# SoC_pwr_1.net
KiCad netlist of a schematic drawn in Altium Designer
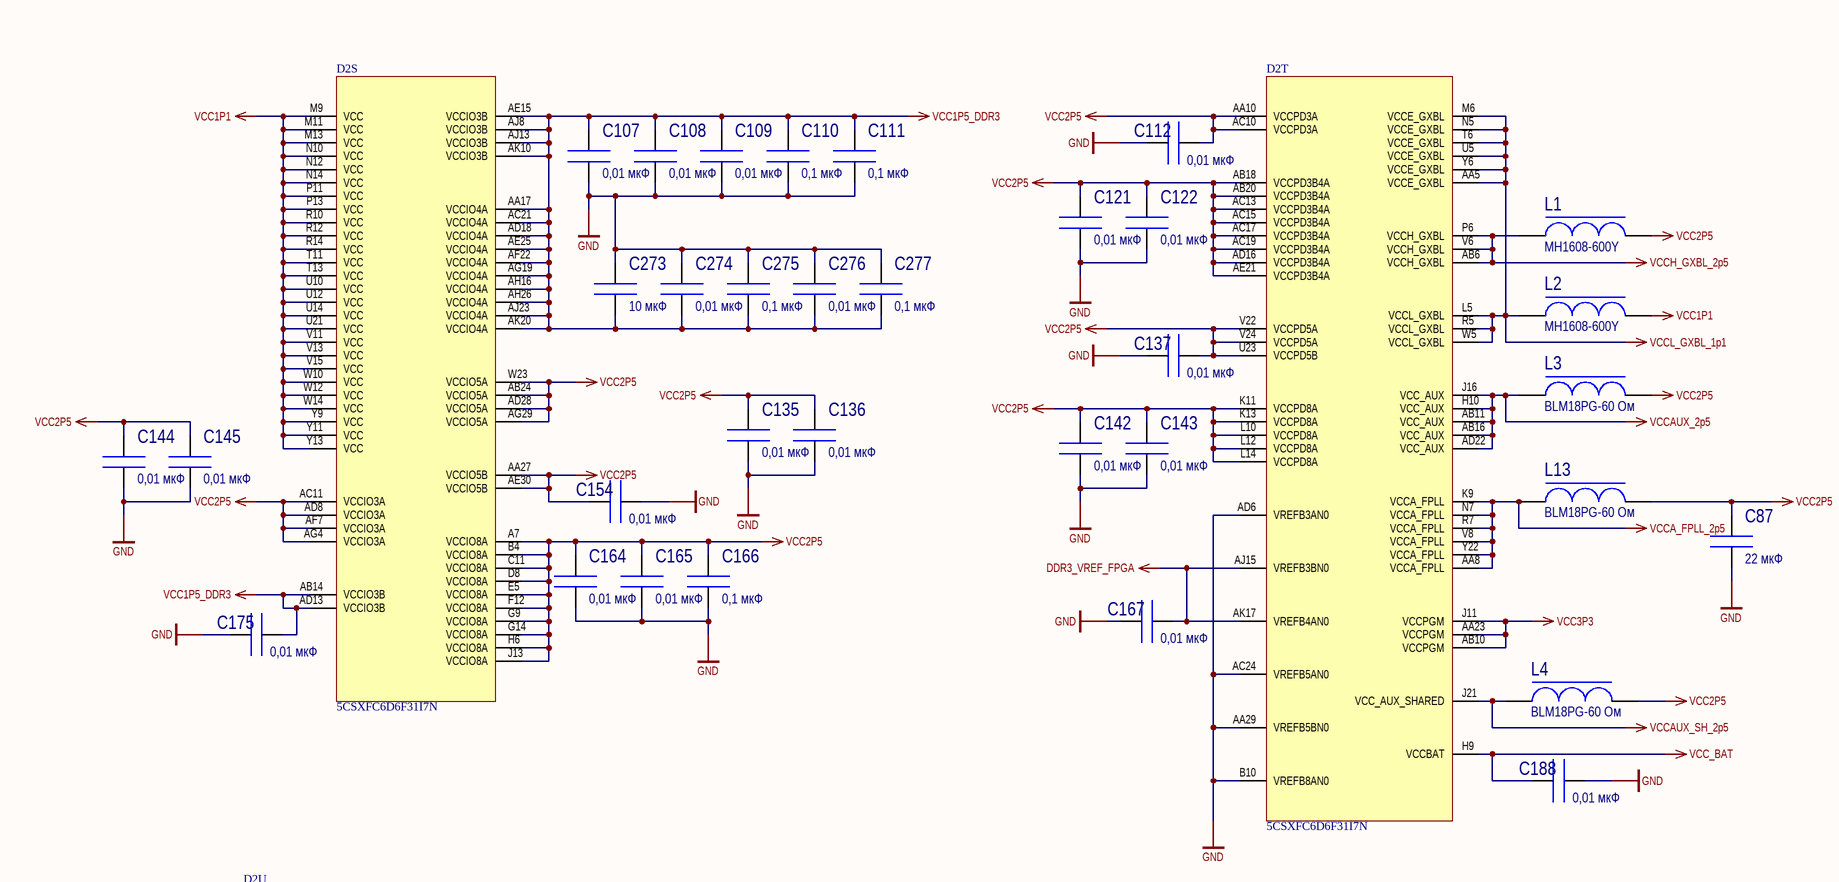
[diagram p0: SoC_pwr_1.SchDoc, top left]
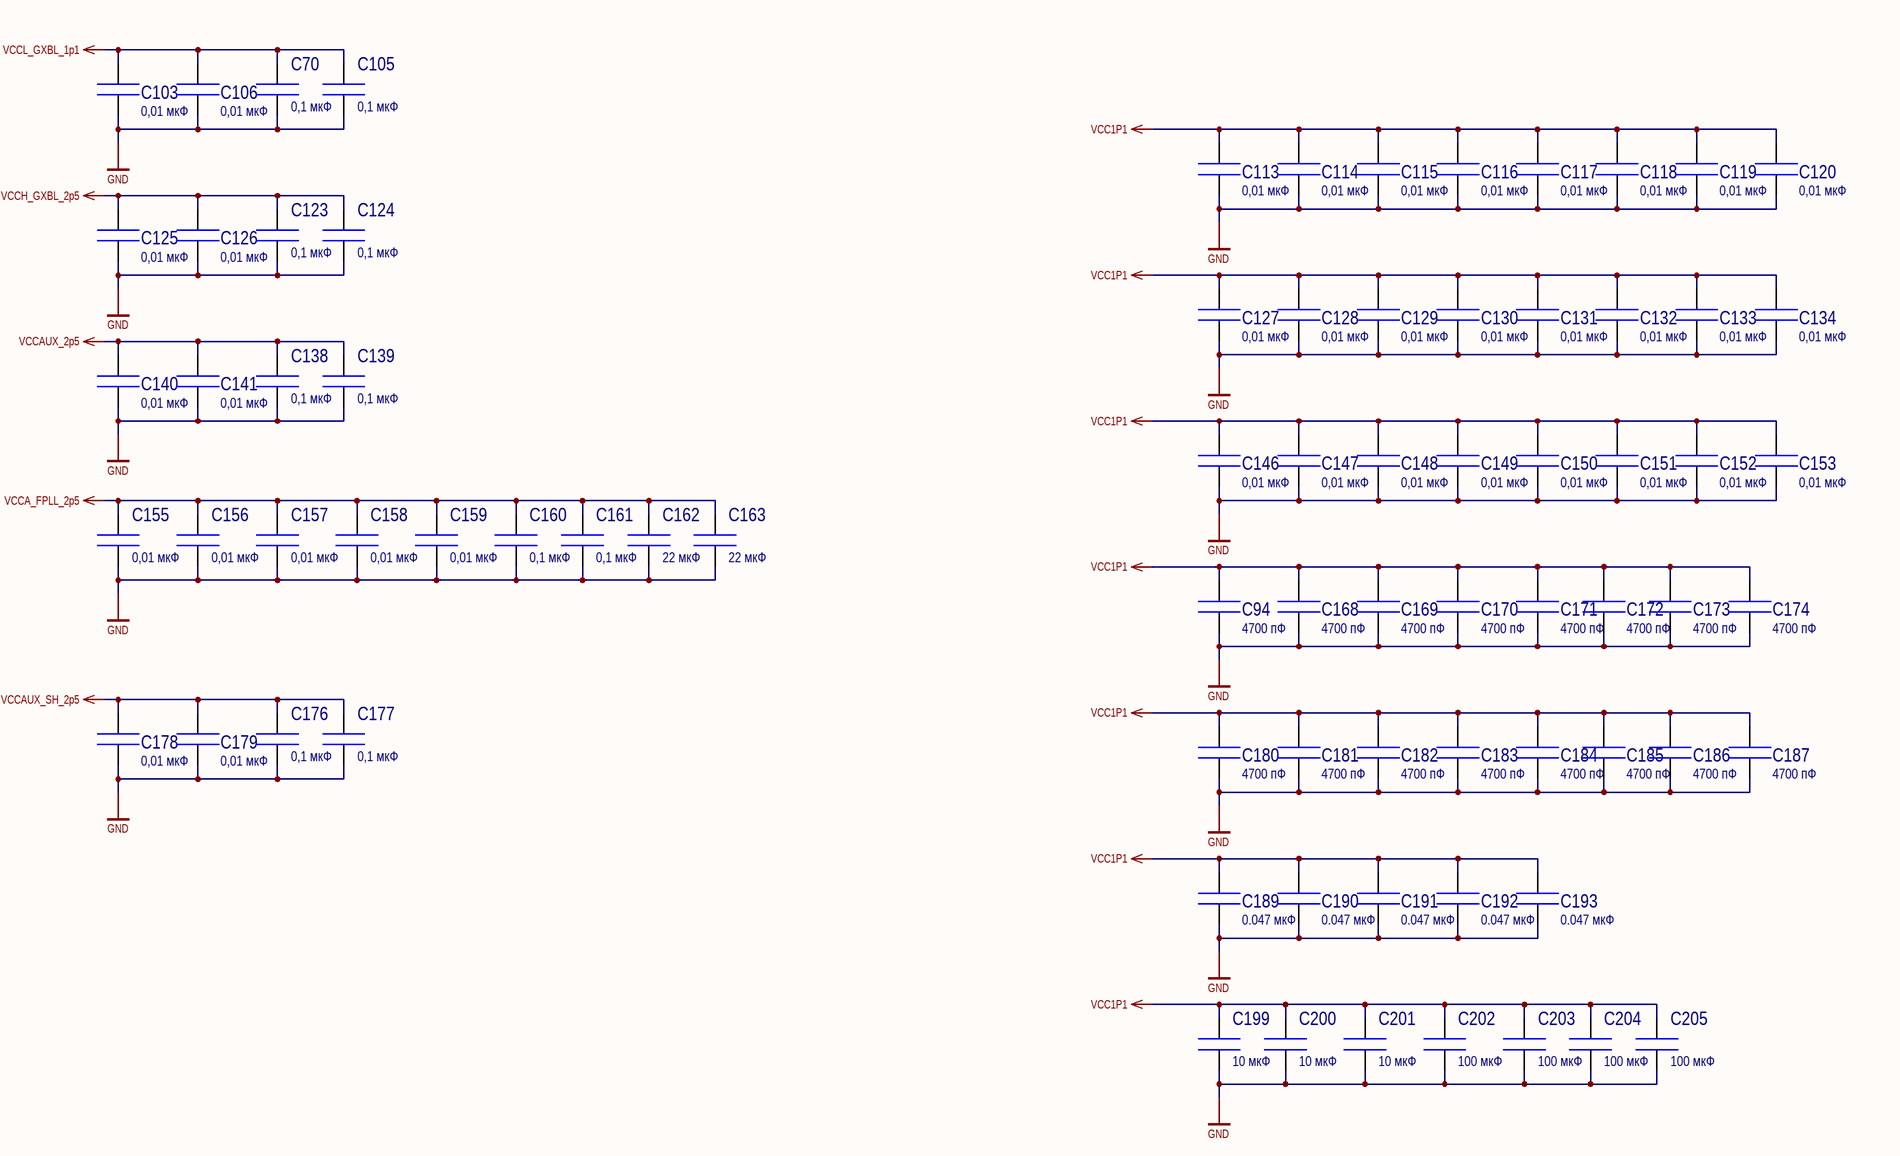
[diagram p1: SoC_pwr_1.SchDoc, top right]
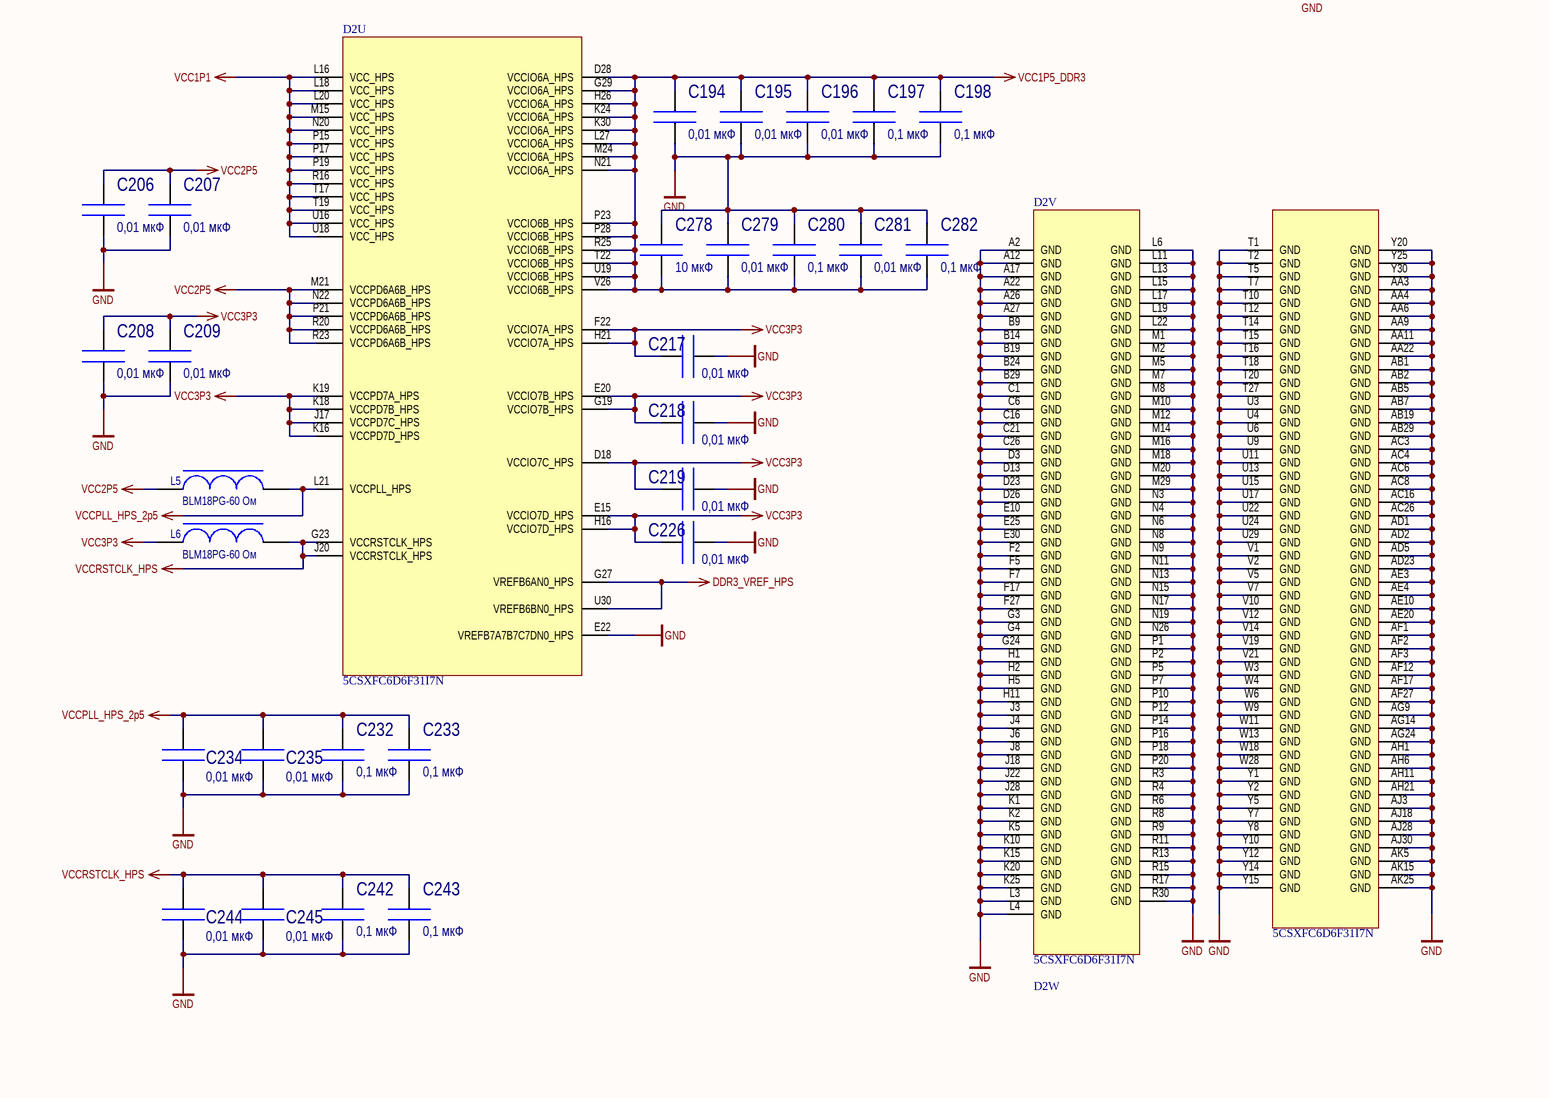
[diagram p2: SoC_pwr_1.SchDoc, bottom left]
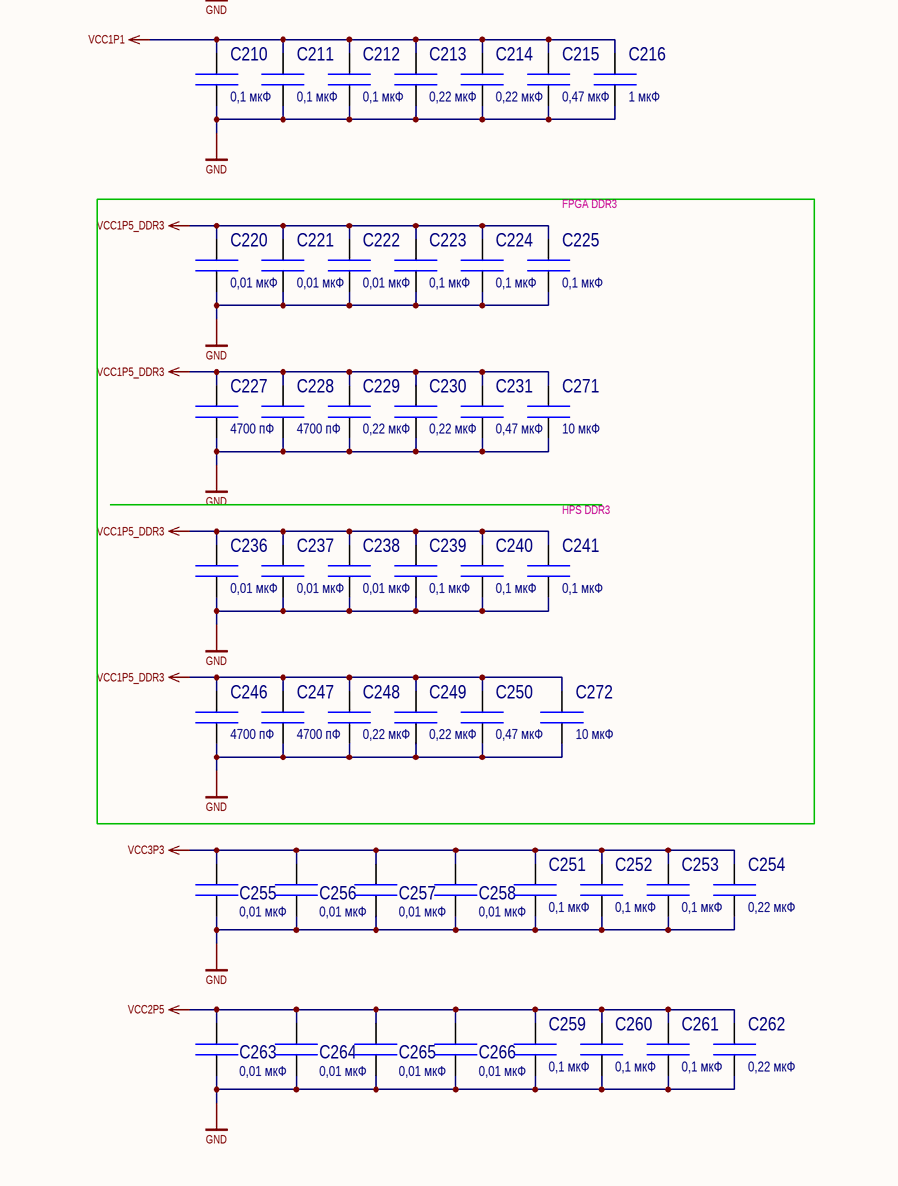
[diagram p3: SoC_pwr_1.SchDoc, bottom right]

(export (version "E")
  (design (tool "Eeschema 10.0.6"))
  (components
    (comp (ref "C70")
      (value "0,1 мкФ")
      (footprint "CC0402(1005)")
      (description "Чип конденсатор керамический")
      (fields (field (name "Comment") "CC0402-X7R-0,1 мкФ-20%-10В"))
      (libsource (lib "Чип конденсаторы") (part "CC0402-X7R-#-20%-10В"))
    )
    (comp (ref "C87")
      (value "22 мкФ")
      (footprint "CC0603")
      (description "Чип конденсатор керамический")
      (fields (field (name "Comment") "CC0603-X5R-22 мкФ-20%-6,3В"))
      (libsource (lib "Конденсаторы") (part "CC0603-X5R-#-20%-6,3В"))
    )
    (comp (ref "C94")
      (value "4700 пФ")
      (footprint "CC0402(1005)")
      (description "Чип конденсатор керамический")
      (fields (field (name "Comment") "CC0402-X7R-4700 пФ-10%-50В"))
      (libsource (lib "Чип конденсаторы") (part "CC0402-X7R-#-20%-10В"))
    )
    (comp (ref "C103")
      (value "0,01 мкФ")
      (footprint "CC0402(1005)")
      (description "Чип конденсатор керамический")
      (fields (field (name "Comment") "CC0402-X7R-0,01 мкФ-10%-50В"))
      (libsource (lib "Чип конденсаторы") (part "CC0402-X7R-#-20%-10В"))
    )
    (comp (ref "C105")
      (value "0,1 мкФ")
      (footprint "CC0402(1005)")
      (description "Чип конденсатор керамический")
      (fields (field (name "Comment") "CC0402-X7R-0,1 мкФ-20%-10В"))
      (libsource (lib "Чип конденсаторы") (part "CC0402-X7R-#-20%-10В"))
    )
    (comp (ref "C106")
      (value "0,01 мкФ")
      (footprint "CC0402(1005)")
      (description "Чип конденсатор керамический")
      (fields (field (name "Comment") "CC0402-X7R-0,01 мкФ-10%-50В"))
      (libsource (lib "Чип конденсаторы") (part "CC0402-X7R-#-20%-10В"))
    )
    (comp (ref "C107")
      (value "0,01 мкФ")
      (footprint "CC0402(1005)")
      (description "Чип конденсатор керамический")
      (fields (field (name "Comment") "CC0402-X7R-0,01 мкФ-10%-50В"))
      (libsource (lib "Чип конденсаторы") (part "CC0402-X7R-#-20%-10В"))
    )
    (comp (ref "C108")
      (value "0,01 мкФ")
      (footprint "CC0402(1005)")
      (description "Чип конденсатор керамический")
      (fields (field (name "Comment") "CC0402-X7R-0,01 мкФ-10%-50В"))
      (libsource (lib "Чип конденсаторы") (part "CC0402-X7R-#-20%-10В"))
    )
    (comp (ref "C109")
      (value "0,01 мкФ")
      (footprint "CC0402(1005)")
      (description "Чип конденсатор керамический")
      (fields (field (name "Comment") "CC0402-X7R-0,01 мкФ-10%-50В"))
      (libsource (lib "Чип конденсаторы") (part "CC0402-X7R-#-20%-10В"))
    )
    (comp (ref "C110")
      (value "0,1 мкФ")
      (footprint "CC0402(1005)")
      (description "Чип конденсатор керамический")
      (fields (field (name "Comment") "CC0402-X7R-0,1 мкФ-20%-10В"))
      (libsource (lib "Чип конденсаторы") (part "CC0402-X7R-#-20%-10В"))
    )
    (comp (ref "C111")
      (value "0,1 мкФ")
      (footprint "CC0402(1005)")
      (description "Чип конденсатор керамический")
      (fields (field (name "Comment") "CC0402-X7R-0,1 мкФ-20%-10В"))
      (libsource (lib "Чип конденсаторы") (part "CC0402-X7R-#-20%-10В"))
    )
    (comp (ref "C112")
      (value "0,01 мкФ")
      (footprint "CC0402(1005)")
      (description "Чип конденсатор керамический")
      (fields (field (name "Comment") "CC0402-X7R-0,01 мкФ-10%-50В"))
      (libsource (lib "Чип конденсаторы") (part "CC0402-X7R-#-20%-10В"))
    )
    (comp (ref "C113")
      (value "0,01 мкФ")
      (footprint "CC0402(1005)")
      (description "Чип конденсатор керамический")
      (fields (field (name "Comment") "CC0402-X7R-0,01 мкФ-10%-50В"))
      (libsource (lib "Чип конденсаторы") (part "CC0402-X7R-#-20%-10В"))
    )
    (comp (ref "C114")
      (value "0,01 мкФ")
      (footprint "CC0402(1005)")
      (description "Чип конденсатор керамический")
      (fields (field (name "Comment") "CC0402-X7R-0,01 мкФ-10%-50В"))
      (libsource (lib "Чип конденсаторы") (part "CC0402-X7R-#-20%-10В"))
    )
    (comp (ref "C115")
      (value "0,01 мкФ")
      (footprint "CC0402(1005)")
      (description "Чип конденсатор керамический")
      (fields (field (name "Comment") "CC0402-X7R-0,01 мкФ-10%-50В"))
      (libsource (lib "Чип конденсаторы") (part "CC0402-X7R-#-20%-10В"))
    )
    (comp (ref "C116")
      (value "0,01 мкФ")
      (footprint "CC0402(1005)")
      (description "Чип конденсатор керамический")
      (fields (field (name "Comment") "CC0402-X7R-0,01 мкФ-10%-50В"))
      (libsource (lib "Чип конденсаторы") (part "CC0402-X7R-#-20%-10В"))
    )
    (comp (ref "C117")
      (value "0,01 мкФ")
      (footprint "CC0402(1005)")
      (description "Чип конденсатор керамический")
      (fields (field (name "Comment") "CC0402-X7R-0,01 мкФ-10%-50В"))
      (libsource (lib "Чип конденсаторы") (part "CC0402-X7R-#-20%-10В"))
    )
    (comp (ref "C118")
      (value "0,01 мкФ")
      (footprint "CC0402(1005)")
      (description "Чип конденсатор керамический")
      (fields (field (name "Comment") "CC0402-X7R-0,01 мкФ-10%-50В"))
      (libsource (lib "Чип конденсаторы") (part "CC0402-X7R-#-20%-10В"))
    )
    (comp (ref "C119")
      (value "0,01 мкФ")
      (footprint "CC0402(1005)")
      (description "Чип конденсатор керамический")
      (fields (field (name "Comment") "CC0402-X7R-0,01 мкФ-10%-50В"))
      (libsource (lib "Чип конденсаторы") (part "CC0402-X7R-#-20%-10В"))
    )
    (comp (ref "C120")
      (value "0,01 мкФ")
      (footprint "CC0402(1005)")
      (description "Чип конденсатор керамический")
      (fields (field (name "Comment") "CC0402-X7R-0,01 мкФ-10%-50В"))
      (libsource (lib "Чип конденсаторы") (part "CC0402-X7R-#-20%-10В"))
    )
    (comp (ref "C121")
      (value "0,01 мкФ")
      (footprint "CC0402(1005)")
      (description "Чип конденсатор керамический")
      (fields (field (name "Comment") "CC0402-X7R-0,01 мкФ-10%-50В"))
      (libsource (lib "Чип конденсаторы") (part "CC0402-X7R-#-20%-10В"))
    )
    (comp (ref "C122")
      (value "0,01 мкФ")
      (footprint "CC0402(1005)")
      (description "Чип конденсатор керамический")
      (fields (field (name "Comment") "CC0402-X7R-0,01 мкФ-10%-50В"))
      (libsource (lib "Чип конденсаторы") (part "CC0402-X7R-#-20%-10В"))
    )
    (comp (ref "C123")
      (value "0,1 мкФ")
      (footprint "CC0402(1005)")
      (description "Чип конденсатор керамический")
      (fields (field (name "Comment") "CC0402-X7R-0,1 мкФ-20%-10В"))
      (libsource (lib "Чип конденсаторы") (part "CC0402-X7R-#-20%-10В"))
    )
    (comp (ref "C124")
      (value "0,1 мкФ")
      (footprint "CC0402(1005)")
      (description "Чип конденсатор керамический")
      (fields (field (name "Comment") "CC0402-X7R-0,1 мкФ-20%-10В"))
      (libsource (lib "Чип конденсаторы") (part "CC0402-X7R-#-20%-10В"))
    )
    (comp (ref "C125")
      (value "0,01 мкФ")
      (footprint "CC0402(1005)")
      (description "Чип конденсатор керамический")
      (fields (field (name "Comment") "CC0402-X7R-0,01 мкФ-10%-50В"))
      (libsource (lib "Чип конденсаторы") (part "CC0402-X7R-#-20%-10В"))
    )
    (comp (ref "C126")
      (value "0,01 мкФ")
      (footprint "CC0402(1005)")
      (description "Чип конденсатор керамический")
      (fields (field (name "Comment") "CC0402-X7R-0,01 мкФ-10%-50В"))
      (libsource (lib "Чип конденсаторы") (part "CC0402-X7R-#-20%-10В"))
    )
    (comp (ref "C127")
      (value "0,01 мкФ")
      (footprint "CC0402(1005)")
      (description "Чип конденсатор керамический")
      (fields (field (name "Comment") "CC0402-X7R-0,01 мкФ-10%-50В"))
      (libsource (lib "Чип конденсаторы") (part "CC0402-X7R-#-20%-10В"))
    )
    (comp (ref "C128")
      (value "0,01 мкФ")
      (footprint "CC0402(1005)")
      (description "Чип конденсатор керамический")
      (fields (field (name "Comment") "CC0402-X7R-0,01 мкФ-10%-50В"))
      (libsource (lib "Чип конденсаторы") (part "CC0402-X7R-#-20%-10В"))
    )
    (comp (ref "C129")
      (value "0,01 мкФ")
      (footprint "CC0402(1005)")
      (description "Чип конденсатор керамический")
      (fields (field (name "Comment") "CC0402-X7R-0,01 мкФ-10%-50В"))
      (libsource (lib "Чип конденсаторы") (part "CC0402-X7R-#-20%-10В"))
    )
    (comp (ref "C130")
      (value "0,01 мкФ")
      (footprint "CC0402(1005)")
      (description "Чип конденсатор керамический")
      (fields (field (name "Comment") "CC0402-X7R-0,01 мкФ-10%-50В"))
      (libsource (lib "Чип конденсаторы") (part "CC0402-X7R-#-20%-10В"))
    )
    (comp (ref "C131")
      (value "0,01 мкФ")
      (footprint "CC0402(1005)")
      (description "Чип конденсатор керамический")
      (fields (field (name "Comment") "CC0402-X7R-0,01 мкФ-10%-50В"))
      (libsource (lib "Чип конденсаторы") (part "CC0402-X7R-#-20%-10В"))
    )
    (comp (ref "C132")
      (value "0,01 мкФ")
      (footprint "CC0402(1005)")
      (description "Чип конденсатор керамический")
      (fields (field (name "Comment") "CC0402-X7R-0,01 мкФ-10%-50В"))
      (libsource (lib "Чип конденсаторы") (part "CC0402-X7R-#-20%-10В"))
    )
    (comp (ref "C133")
      (value "0,01 мкФ")
      (footprint "CC0402(1005)")
      (description "Чип конденсатор керамический")
      (fields (field (name "Comment") "CC0402-X7R-0,01 мкФ-10%-50В"))
      (libsource (lib "Чип конденсаторы") (part "CC0402-X7R-#-20%-10В"))
    )
    (comp (ref "C134")
      (value "0,01 мкФ")
      (footprint "CC0402(1005)")
      (description "Чип конденсатор керамический")
      (fields (field (name "Comment") "CC0402-X7R-0,01 мкФ-10%-50В"))
      (libsource (lib "Чип конденсаторы") (part "CC0402-X7R-#-20%-10В"))
    )
    (comp (ref "C135")
      (value "0,01 мкФ")
      (footprint "CC0402(1005)")
      (description "Чип конденсатор керамический")
      (fields (field (name "Comment") "CC0402-X7R-0,01 мкФ-10%-50В"))
      (libsource (lib "Чип конденсаторы") (part "CC0402-X7R-#-20%-10В"))
    )
    (comp (ref "C136")
      (value "0,01 мкФ")
      (footprint "CC0402(1005)")
      (description "Чип конденсатор керамический")
      (fields (field (name "Comment") "CC0402-X7R-0,01 мкФ-10%-50В"))
      (libsource (lib "Чип конденсаторы") (part "CC0402-X7R-#-20%-10В"))
    )
    (comp (ref "C137")
      (value "0,01 мкФ")
      (footprint "CC0402(1005)")
      (description "Чип конденсатор керамический")
      (fields (field (name "Comment") "CC0402-X7R-0,01 мкФ-10%-50В"))
      (libsource (lib "Чип конденсаторы") (part "CC0402-X7R-#-20%-10В"))
    )
    (comp (ref "C138")
      (value "0,1 мкФ")
      (footprint "CC0402(1005)")
      (description "Чип конденсатор керамический")
      (fields (field (name "Comment") "CC0402-X7R-0,1 мкФ-20%-10В"))
      (libsource (lib "Чип конденсаторы") (part "CC0402-X7R-#-20%-10В"))
    )
    (comp (ref "C139")
      (value "0,1 мкФ")
      (footprint "CC0402(1005)")
      (description "Чип конденсатор керамический")
      (fields (field (name "Comment") "CC0402-X7R-0,1 мкФ-20%-10В"))
      (libsource (lib "Чип конденсаторы") (part "CC0402-X7R-#-20%-10В"))
    )
    (comp (ref "C140")
      (value "0,01 мкФ")
      (footprint "CC0402(1005)")
      (description "Чип конденсатор керамический")
      (fields (field (name "Comment") "CC0402-X7R-0,01 мкФ-10%-50В"))
      (libsource (lib "Чип конденсаторы") (part "CC0402-X7R-#-20%-10В"))
    )
    (comp (ref "C141")
      (value "0,01 мкФ")
      (footprint "CC0402(1005)")
      (description "Чип конденсатор керамический")
      (fields (field (name "Comment") "CC0402-X7R-0,01 мкФ-10%-50В"))
      (libsource (lib "Чип конденсаторы") (part "CC0402-X7R-#-20%-10В"))
    )
    (comp (ref "C142")
      (value "0,01 мкФ")
      (footprint "CC0402(1005)")
      (description "Чип конденсатор керамический")
      (fields (field (name "Comment") "CC0402-X7R-0,01 мкФ-10%-50В"))
      (libsource (lib "Чип конденсаторы") (part "CC0402-X7R-#-20%-10В"))
    )
    (comp (ref "C143")
      (value "0,01 мкФ")
      (footprint "CC0402(1005)")
      (description "Чип конденсатор керамический")
      (fields (field (name "Comment") "CC0402-X7R-0,01 мкФ-10%-50В"))
      (libsource (lib "Чип конденсаторы") (part "CC0402-X7R-#-20%-10В"))
    )
    (comp (ref "C144")
      (value "0,01 мкФ")
      (footprint "CC0402(1005)")
      (description "Чип конденсатор керамический")
      (fields (field (name "Comment") "CC0402-X7R-0,01 мкФ-10%-50В"))
      (libsource (lib "Чип конденсаторы") (part "CC0402-X7R-#-20%-10В"))
    )
    (comp (ref "C145")
      (value "0,01 мкФ")
      (footprint "CC0402(1005)")
      (description "Чип конденсатор керамический")
      (fields (field (name "Comment") "CC0402-X7R-0,01 мкФ-10%-50В"))
      (libsource (lib "Чип конденсаторы") (part "CC0402-X7R-#-20%-10В"))
    )
    (comp (ref "C146")
      (value "0,01 мкФ")
      (footprint "CC0402(1005)")
      (description "Чип конденсатор керамический")
      (fields (field (name "Comment") "CC0402-X7R-0,01 мкФ-10%-50В"))
      (libsource (lib "Чип конденсаторы") (part "CC0402-X7R-#-20%-10В"))
    )
    (comp (ref "C147")
      (value "0,01 мкФ")
      (footprint "CC0402(1005)")
      (description "Чип конденсатор керамический")
      (fields (field (name "Comment") "CC0402-X7R-0,01 мкФ-10%-50В"))
      (libsource (lib "Чип конденсаторы") (part "CC0402-X7R-#-20%-10В"))
    )
    (comp (ref "C148")
      (value "0,01 мкФ")
      (footprint "CC0402(1005)")
      (description "Чип конденсатор керамический")
      (fields (field (name "Comment") "CC0402-X7R-0,01 мкФ-10%-50В"))
      (libsource (lib "Чип конденсаторы") (part "CC0402-X7R-#-20%-10В"))
    )
    (comp (ref "C149")
      (value "0,01 мкФ")
      (footprint "CC0402(1005)")
      (description "Чип конденсатор керамический")
      (fields (field (name "Comment") "CC0402-X7R-0,01 мкФ-10%-50В"))
      (libsource (lib "Чип конденсаторы") (part "CC0402-X7R-#-20%-10В"))
    )
    (comp (ref "C150")
      (value "0,01 мкФ")
      (footprint "CC0402(1005)")
      (description "Чип конденсатор керамический")
      (fields (field (name "Comment") "CC0402-X7R-0,01 мкФ-10%-50В"))
      (libsource (lib "Чип конденсаторы") (part "CC0402-X7R-#-20%-10В"))
    )
    (comp (ref "C151")
      (value "0,01 мкФ")
      (footprint "CC0402(1005)")
      (description "Чип конденсатор керамический")
      (fields (field (name "Comment") "CC0402-X7R-0,01 мкФ-10%-50В"))
      (libsource (lib "Чип конденсаторы") (part "CC0402-X7R-#-20%-10В"))
    )
    (comp (ref "C152")
      (value "0,01 мкФ")
      (footprint "CC0402(1005)")
      (description "Чип конденсатор керамический")
      (fields (field (name "Comment") "CC0402-X7R-0,01 мкФ-10%-50В"))
      (libsource (lib "Чип конденсаторы") (part "CC0402-X7R-#-20%-10В"))
    )
    (comp (ref "C153")
      (value "0,01 мкФ")
      (footprint "CC0402(1005)")
      (description "Чип конденсатор керамический")
      (fields (field (name "Comment") "CC0402-X7R-0,01 мкФ-10%-50В"))
      (libsource (lib "Чип конденсаторы") (part "CC0402-X7R-#-20%-10В"))
    )
    (comp (ref "C154")
      (value "0,01 мкФ")
      (footprint "CC0402(1005)")
      (description "Чип конденсатор керамический")
      (fields (field (name "Comment") "CC0402-X7R-0,01 мкФ-10%-50В"))
      (libsource (lib "Чип конденсаторы") (part "CC0402-X7R-#-20%-10В"))
    )
    (comp (ref "C155")
      (value "0,01 мкФ")
      (footprint "CC0402(1005)")
      (description "Чип конденсатор керамический")
      (fields (field (name "Comment") "CC0402-X7R-0,01 мкФ-10%-50В"))
      (libsource (lib "Чип конденсаторы") (part "CC0402-X7R-#-20%-10В"))
    )
    (comp (ref "C156")
      (value "0,01 мкФ")
      (footprint "CC0402(1005)")
      (description "Чип конденсатор керамический")
      (fields (field (name "Comment") "CC0402-X7R-0,01 мкФ-10%-50В"))
      (libsource (lib "Чип конденсаторы") (part "CC0402-X7R-#-20%-10В"))
    )
    (comp (ref "C157")
      (value "0,01 мкФ")
      (footprint "CC0402(1005)")
      (description "Чип конденсатор керамический")
      (fields (field (name "Comment") "CC0402-X7R-0,01 мкФ-10%-50В"))
      (libsource (lib "Чип конденсаторы") (part "CC0402-X7R-#-20%-10В"))
    )
    (comp (ref "C158")
      (value "0,01 мкФ")
      (footprint "CC0402(1005)")
      (description "Чип конденсатор керамический")
      (fields (field (name "Comment") "CC0402-X7R-0,01 мкФ-10%-50В"))
      (libsource (lib "Чип конденсаторы") (part "CC0402-X7R-#-20%-10В"))
    )
    (comp (ref "C159")
      (value "0,01 мкФ")
      (footprint "CC0402(1005)")
      (description "Чип конденсатор керамический")
      (fields (field (name "Comment") "CC0402-X7R-0,01 мкФ-10%-50В"))
      (libsource (lib "Чип конденсаторы") (part "CC0402-X7R-#-20%-10В"))
    )
    (comp (ref "C160")
      (value "0,1 мкФ")
      (footprint "CC0402(1005)")
      (description "Чип конденсатор керамический")
      (fields (field (name "Comment") "CC0402-X7R-0,1 мкФ-20%-10В"))
      (libsource (lib "Чип конденсаторы") (part "CC0402-X7R-#-20%-10В"))
    )
    (comp (ref "C161")
      (value "0,1 мкФ")
      (footprint "CC0402(1005)")
      (description "Чип конденсатор керамический")
      (fields (field (name "Comment") "CC0402-X7R-0,1 мкФ-20%-10В"))
      (libsource (lib "Чип конденсаторы") (part "CC0402-X7R-#-20%-10В"))
    )
    (comp (ref "C162")
      (value "22 мкФ")
      (footprint "CC0603")
      (description "Чип конденсатор керамический")
      (fields (field (name "Comment") "CC0603-X5R-22 мкФ-20%-6,3В"))
      (libsource (lib "Конденсаторы") (part "CC0603-X5R-#-20%-6,3В"))
    )
    (comp (ref "C163")
      (value "22 мкФ")
      (footprint "CC0603")
      (description "Чип конденсатор керамический")
      (fields (field (name "Comment") "CC0603-X5R-22 мкФ-20%-6,3В"))
      (libsource (lib "Конденсаторы") (part "CC0603-X5R-#-20%-6,3В"))
    )
    (comp (ref "C164")
      (value "0,01 мкФ")
      (footprint "CC0402(1005)")
      (description "Чип конденсатор керамический")
      (fields (field (name "Comment") "CC0402-X7R-0,01 мкФ-10%-50В"))
      (libsource (lib "Чип конденсаторы") (part "CC0402-X7R-#-20%-10В"))
    )
    (comp (ref "C165")
      (value "0,01 мкФ")
      (footprint "CC0402(1005)")
      (description "Чип конденсатор керамический")
      (fields (field (name "Comment") "CC0402-X7R-0,01 мкФ-10%-50В"))
      (libsource (lib "Чип конденсаторы") (part "CC0402-X7R-#-20%-10В"))
    )
    (comp (ref "C166")
      (value "0,1 мкФ")
      (footprint "CC0402(1005)")
      (description "Чип конденсатор керамический")
      (fields (field (name "Comment") "CC0402-X7R-0,1 мкФ-20%-10В"))
      (libsource (lib "Чип конденсаторы") (part "CC0402-X7R-#-20%-10В"))
    )
    (comp (ref "C167")
      (value "0,01 мкФ")
      (footprint "CC0402(1005)")
      (description "Чип конденсатор керамический")
      (fields (field (name "Comment") "CC0402-X7R-0,01 мкФ-10%-50В"))
      (libsource (lib "Чип конденсаторы") (part "CC0402-X7R-#-20%-10В"))
    )
    (comp (ref "C168")
      (value "4700 пФ")
      (footprint "CC0402(1005)")
      (description "Чип конденсатор керамический")
      (fields (field (name "Comment") "CC0402-X7R-4700 пФ-10%-50В"))
      (libsource (lib "Чип конденсаторы") (part "CC0402-X7R-#-20%-10В"))
    )
    (comp (ref "C169")
      (value "4700 пФ")
      (footprint "CC0402(1005)")
      (description "Чип конденсатор керамический")
      (fields (field (name "Comment") "CC0402-X7R-4700 пФ-10%-50В"))
      (libsource (lib "Чип конденсаторы") (part "CC0402-X7R-#-20%-10В"))
    )
    (comp (ref "C170")
      (value "4700 пФ")
      (footprint "CC0402(1005)")
      (description "Чип конденсатор керамический")
      (fields (field (name "Comment") "CC0402-X7R-4700 пФ-10%-50В"))
      (libsource (lib "Чип конденсаторы") (part "CC0402-X7R-#-20%-10В"))
    )
    (comp (ref "C171")
      (value "4700 пФ")
      (footprint "CC0402(1005)")
      (description "Чип конденсатор керамический")
      (fields (field (name "Comment") "CC0402-X7R-4700 пФ-10%-50В"))
      (libsource (lib "Чип конденсаторы") (part "CC0402-X7R-#-20%-10В"))
    )
    (comp (ref "C172")
      (value "4700 пФ")
      (footprint "CC0402(1005)")
      (description "Чип конденсатор керамический")
      (fields (field (name "Comment") "CC0402-X7R-4700 пФ-10%-50В"))
      (libsource (lib "Чип конденсаторы") (part "CC0402-X7R-#-20%-10В"))
    )
    (comp (ref "C173")
      (value "4700 пФ")
      (footprint "CC0402(1005)")
      (description "Чип конденсатор керамический")
      (fields (field (name "Comment") "CC0402-X7R-4700 пФ-10%-50В"))
      (libsource (lib "Чип конденсаторы") (part "CC0402-X7R-#-20%-10В"))
    )
    (comp (ref "C174")
      (value "4700 пФ")
      (footprint "CC0402(1005)")
      (description "Чип конденсатор керамический")
      (fields (field (name "Comment") "CC0402-X7R-4700 пФ-10%-50В"))
      (libsource (lib "Чип конденсаторы") (part "CC0402-X7R-#-20%-10В"))
    )
    (comp (ref "C175")
      (value "0,01 мкФ")
      (footprint "CC0402(1005)")
      (description "Чип конденсатор керамический")
      (fields (field (name "Comment") "CC0402-X7R-0,01 мкФ-10%-50В"))
      (libsource (lib "Чип конденсаторы") (part "CC0402-X7R-#-20%-10В"))
    )
    (comp (ref "C176")
      (value "0,1 мкФ")
      (footprint "CC0402(1005)")
      (description "Чип конденсатор керамический")
      (fields (field (name "Comment") "CC0402-X7R-0,1 мкФ-20%-10В"))
      (libsource (lib "Чип конденсаторы") (part "CC0402-X7R-#-20%-10В"))
    )
    (comp (ref "C177")
      (value "0,1 мкФ")
      (footprint "CC0402(1005)")
      (description "Чип конденсатор керамический")
      (fields (field (name "Comment") "CC0402-X7R-0,1 мкФ-20%-10В"))
      (libsource (lib "Чип конденсаторы") (part "CC0402-X7R-#-20%-10В"))
    )
    (comp (ref "C178")
      (value "0,01 мкФ")
      (footprint "CC0402(1005)")
      (description "Чип конденсатор керамический")
      (fields (field (name "Comment") "CC0402-X7R-0,01 мкФ-10%-50В"))
      (libsource (lib "Чип конденсаторы") (part "CC0402-X7R-#-20%-10В"))
    )
    (comp (ref "C179")
      (value "0,01 мкФ")
      (footprint "CC0402(1005)")
      (description "Чип конденсатор керамический")
      (fields (field (name "Comment") "CC0402-X7R-0,01 мкФ-10%-50В"))
      (libsource (lib "Чип конденсаторы") (part "CC0402-X7R-#-20%-10В"))
    )
    (comp (ref "C180")
      (value "4700 пФ")
      (footprint "CC0402(1005)")
      (description "Чип конденсатор керамический")
      (fields (field (name "Comment") "CC0402-X7R-4700 пФ-10%-50В"))
      (libsource (lib "Чип конденсаторы") (part "CC0402-X7R-#-20%-10В"))
    )
    (comp (ref "C181")
      (value "4700 пФ")
      (footprint "CC0402(1005)")
      (description "Чип конденсатор керамический")
      (fields (field (name "Comment") "CC0402-X7R-4700 пФ-10%-50В"))
      (libsource (lib "Чип конденсаторы") (part "CC0402-X7R-#-20%-10В"))
    )
    (comp (ref "C182")
      (value "4700 пФ")
      (footprint "CC0402(1005)")
      (description "Чип конденсатор керамический")
      (fields (field (name "Comment") "CC0402-X7R-4700 пФ-10%-50В"))
      (libsource (lib "Чип конденсаторы") (part "CC0402-X7R-#-20%-10В"))
    )
    (comp (ref "C183")
      (value "4700 пФ")
      (footprint "CC0402(1005)")
      (description "Чип конденсатор керамический")
      (fields (field (name "Comment") "CC0402-X7R-4700 пФ-10%-50В"))
      (libsource (lib "Чип конденсаторы") (part "CC0402-X7R-#-20%-10В"))
    )
    (comp (ref "C184")
      (value "4700 пФ")
      (footprint "CC0402(1005)")
      (description "Чип конденсатор керамический")
      (fields (field (name "Comment") "CC0402-X7R-4700 пФ-10%-50В"))
      (libsource (lib "Чип конденсаторы") (part "CC0402-X7R-#-20%-10В"))
    )
    (comp (ref "C185")
      (value "4700 пФ")
      (footprint "CC0402(1005)")
      (description "Чип конденсатор керамический")
      (fields (field (name "Comment") "CC0402-X7R-4700 пФ-10%-50В"))
      (libsource (lib "Чип конденсаторы") (part "CC0402-X7R-#-20%-10В"))
    )
    (comp (ref "C186")
      (value "4700 пФ")
      (footprint "CC0402(1005)")
      (description "Чип конденсатор керамический")
      (fields (field (name "Comment") "CC0402-X7R-4700 пФ-10%-50В"))
      (libsource (lib "Чип конденсаторы") (part "CC0402-X7R-#-20%-10В"))
    )
    (comp (ref "C187")
      (value "4700 пФ")
      (footprint "CC0402(1005)")
      (description "Чип конденсатор керамический")
      (fields (field (name "Comment") "CC0402-X7R-4700 пФ-10%-50В"))
      (libsource (lib "Чип конденсаторы") (part "CC0402-X7R-#-20%-10В"))
    )
    (comp (ref "C188")
      (value "0,01 мкФ")
      (footprint "CC0402(1005)")
      (description "Чип конденсатор керамический")
      (fields (field (name "Comment") "CC0402-X7R-0,01 мкФ-10%-50В"))
      (libsource (lib "Чип конденсаторы") (part "CC0402-X7R-#-20%-10В"))
    )
    (comp (ref "C189")
      (value "0.047 мкФ")
      (footprint "CC0402(1005)")
      (description "Чип конденсатор керамический")
      (fields (field (name "Comment") "CC0402-X7R-0.047 мкФ-10%-50В"))
      (libsource (lib "Чип конденсаторы") (part "CC0402-X7R-#-20%-10В"))
    )
    (comp (ref "C190")
      (value "0.047 мкФ")
      (footprint "CC0402(1005)")
      (description "Чип конденсатор керамический")
      (fields (field (name "Comment") "CC0402-X7R-0.047 мкФ-10%-50В"))
      (libsource (lib "Чип конденсаторы") (part "CC0402-X7R-#-20%-10В"))
    )
    (comp (ref "C191")
      (value "0.047 мкФ")
      (footprint "CC0402(1005)")
      (description "Чип конденсатор керамический")
      (fields (field (name "Comment") "CC0402-X7R-0.047 мкФ-10%-50В"))
      (libsource (lib "Чип конденсаторы") (part "CC0402-X7R-#-20%-10В"))
    )
    (comp (ref "C192")
      (value "0.047 мкФ")
      (footprint "CC0402(1005)")
      (description "Чип конденсатор керамический")
      (fields (field (name "Comment") "CC0402-X7R-0.047 мкФ-10%-50В"))
      (libsource (lib "Чип конденсаторы") (part "CC0402-X7R-#-20%-10В"))
    )
    (comp (ref "C193")
      (value "0.047 мкФ")
      (footprint "CC0402(1005)")
      (description "Чип конденсатор керамический")
      (fields (field (name "Comment") "CC0402-X7R-0.047 мкФ-10%-50В"))
      (libsource (lib "Чип конденсаторы") (part "CC0402-X7R-#-20%-10В"))
    )
    (comp (ref "C194")
      (value "0,01 мкФ")
      (footprint "CC0402(1005)")
      (description "Чип конденсатор керамический")
      (fields (field (name "Comment") "CC0402-X7R-0,01 мкФ-10%-50В"))
      (libsource (lib "Чип конденсаторы") (part "CC0402-X7R-#-20%-10В"))
    )
    (comp (ref "C195")
      (value "0,01 мкФ")
      (footprint "CC0402(1005)")
      (description "Чип конденсатор керамический")
      (fields (field (name "Comment") "CC0402-X7R-0,01 мкФ-10%-50В"))
      (libsource (lib "Чип конденсаторы") (part "CC0402-X7R-#-20%-10В"))
    )
    (comp (ref "C196")
      (value "0,01 мкФ")
      (footprint "CC0402(1005)")
      (description "Чип конденсатор керамический")
      (fields (field (name "Comment") "CC0402-X7R-0,01 мкФ-10%-50В"))
      (libsource (lib "Чип конденсаторы") (part "CC0402-X7R-#-20%-10В"))
    )
    (comp (ref "C197")
      (value "0,1 мкФ")
      (footprint "CC0402(1005)")
      (description "Чип конденсатор керамический")
      (fields (field (name "Comment") "CC0402-X7R-0,1 мкФ-20%-10В"))
      (libsource (lib "Чип конденсаторы") (part "CC0402-X7R-#-20%-10В"))
    )
    (comp (ref "C198")
      (value "0,1 мкФ")
      (footprint "CC0402(1005)")
      (description "Чип конденсатор керамический")
      (fields (field (name "Comment") "CC0402-X7R-0,1 мкФ-20%-10В"))
      (libsource (lib "Чип конденсаторы") (part "CC0402-X7R-#-20%-10В"))
    )
    (comp (ref "C199")
      (value "10 мкФ")
      (footprint "CC0402(1005)")
      (description "Чип конденсатор керамический")
      (fields (field (name "Comment") "CC0402-X5R-10 мкФ-20%-6.3В"))
      (libsource (lib "Чип конденсаторы") (part "CC0402-X7R-#-20%-10В"))
    )
    (comp (ref "C200")
      (value "10 мкФ")
      (footprint "CC0402(1005)")
      (description "Чип конденсатор керамический")
      (fields (field (name "Comment") "CC0402-X5R-10 мкФ-20%-6.3В"))
      (libsource (lib "Чип конденсаторы") (part "CC0402-X7R-#-20%-10В"))
    )
    (comp (ref "C201")
      (value "10 мкФ")
      (footprint "CC0402(1005)")
      (description "Чип конденсатор керамический")
      (fields (field (name "Comment") "CC0402-X5R-10 мкФ-20%-6.3В"))
      (libsource (lib "Чип конденсаторы") (part "CC0402-X7R-#-20%-10В"))
    )
    (comp (ref "C202")
      (value "100 мкФ")
      (footprint "CC0805")
      (description "Чип конденсатор керамический")
      (fields (field (name "Comment") "CC0805-X5R-100 мкФ-20%-4В"))
      (libsource (lib "Конденсаторы") (part "CC0805-X7R-#-20%-25В"))
    )
    (comp (ref "C203")
      (value "100 мкФ")
      (footprint "CC0805")
      (description "Чип конденсатор керамический")
      (fields (field (name "Comment") "CC0805-X5R-100 мкФ-20%-4В"))
      (libsource (lib "Конденсаторы") (part "CC0805-X7R-#-20%-25В"))
    )
    (comp (ref "C204")
      (value "100 мкФ")
      (footprint "CC0805")
      (description "Чип конденсатор керамический")
      (fields (field (name "Comment") "CC0805-X5R-100 мкФ-20%-4В"))
      (libsource (lib "Конденсаторы") (part "CC0805-X7R-#-20%-25В"))
    )
    (comp (ref "C205")
      (value "100 мкФ")
      (footprint "CC0805")
      (description "Чип конденсатор керамический")
      (fields (field (name "Comment") "CC0805-X5R-100 мкФ-20%-4В"))
      (libsource (lib "Конденсаторы") (part "CC0805-X7R-#-20%-25В"))
    )
    (comp (ref "C206")
      (value "0,01 мкФ")
      (footprint "CC0402(1005)")
      (description "Чип конденсатор керамический")
      (fields (field (name "Comment") "CC0402-X7R-0,01 мкФ-10%-50В"))
      (libsource (lib "Чип конденсаторы") (part "CC0402-X7R-#-20%-10В"))
    )
    (comp (ref "C207")
      (value "0,01 мкФ")
      (footprint "CC0402(1005)")
      (description "Чип конденсатор керамический")
      (fields (field (name "Comment") "CC0402-X7R-0,01 мкФ-10%-50В"))
      (libsource (lib "Чип конденсаторы") (part "CC0402-X7R-#-20%-10В"))
    )
    (comp (ref "C208")
      (value "0,01 мкФ")
      (footprint "CC0402(1005)")
      (description "Чип конденсатор керамический")
      (fields (field (name "Comment") "CC0402-X7R-0,01 мкФ-10%-50В"))
      (libsource (lib "Чип конденсаторы") (part "CC0402-X7R-#-20%-10В"))
    )
    (comp (ref "C209")
      (value "0,01 мкФ")
      (footprint "CC0402(1005)")
      (description "Чип конденсатор керамический")
      (fields (field (name "Comment") "CC0402-X7R-0,01 мкФ-10%-50В"))
      (libsource (lib "Чип конденсаторы") (part "CC0402-X7R-#-20%-10В"))
    )
    (comp (ref "C210")
      (value "0,1 мкФ")
      (footprint "CC0402(1005)")
      (description "Чип конденсатор керамический")
      (fields (field (name "Comment") "CC0402-X7R-0,1 мкФ-20%-10В"))
      (libsource (lib "Чип конденсаторы") (part "CC0402-X7R-#-20%-10В"))
    )
    (comp (ref "C211")
      (value "0,1 мкФ")
      (footprint "CC0402(1005)")
      (description "Чип конденсатор керамический")
      (fields (field (name "Comment") "CC0402-X7R-0,1 мкФ-20%-10В"))
      (libsource (lib "Чип конденсаторы") (part "CC0402-X7R-#-20%-10В"))
    )
    (comp (ref "C212")
      (value "0,1 мкФ")
      (footprint "CC0402(1005)")
      (description "Чип конденсатор керамический")
      (fields (field (name "Comment") "CC0402-X7R-0,1 мкФ-20%-10В"))
      (libsource (lib "Чип конденсаторы") (part "CC0402-X7R-#-20%-10В"))
    )
    (comp (ref "C213")
      (value "0,22 мкФ")
      (footprint "CC0402(1005)")
      (description "Чип конденсатор керамический")
      (fields (field (name "Comment") "CC0402-X7R-0,22 мкФ-10%-6.3В"))
      (libsource (lib "Чип конденсаторы") (part "CC0402-X7R-#-20%-10В"))
    )
    (comp (ref "C214")
      (value "0,22 мкФ")
      (footprint "CC0402(1005)")
      (description "Чип конденсатор керамический")
      (fields (field (name "Comment") "CC0402-X7R-0,22 мкФ-10%-6.3В"))
      (libsource (lib "Чип конденсаторы") (part "CC0402-X7R-#-20%-10В"))
    )
    (comp (ref "C215")
      (value "0,47 мкФ")
      (footprint "CC0402(1005)")
      (description "Чип конденсатор керамический")
      (fields (field (name "Comment") "CC0402-X7R-0,47 мкФ-10%-6.3В"))
      (libsource (lib "Чип конденсаторы") (part "CC0402-X7R-#-20%-10В"))
    )
    (comp (ref "C216")
      (value "1 мкФ")
      (footprint "CC0402(1005)")
      (description "Чип конденсатор керамический")
      (fields (field (name "Comment") "CC0402-X5R-1 мкФ-10%-6.3В"))
      (libsource (lib "Чип конденсаторы") (part "CC0402-X7R-#-20%-10В"))
    )
    (comp (ref "C217")
      (value "0,01 мкФ")
      (footprint "CC0402(1005)")
      (description "Чип конденсатор керамический")
      (fields (field (name "Comment") "CC0402-X7R-0,01 мкФ-10%-50В"))
      (libsource (lib "Чип конденсаторы") (part "CC0402-X7R-#-20%-10В"))
    )
    (comp (ref "C218")
      (value "0,01 мкФ")
      (footprint "CC0402(1005)")
      (description "Чип конденсатор керамический")
      (fields (field (name "Comment") "CC0402-X7R-0,01 мкФ-10%-50В"))
      (libsource (lib "Чип конденсаторы") (part "CC0402-X7R-#-20%-10В"))
    )
    (comp (ref "C219")
      (value "0,01 мкФ")
      (footprint "CC0402(1005)")
      (description "Чип конденсатор керамический")
      (fields (field (name "Comment") "CC0402-X7R-0,01 мкФ-10%-50В"))
      (libsource (lib "Чип конденсаторы") (part "CC0402-X7R-#-20%-10В"))
    )
    (comp (ref "C220")
      (value "0,01 мкФ")
      (footprint "CC0402(1005)")
      (description "Чип конденсатор керамический")
      (fields (field (name "Comment") "CC0402-X7R-0,01 мкФ-10%-50В"))
      (libsource (lib "Чип конденсаторы") (part "CC0402-X7R-#-20%-10В"))
    )
    (comp (ref "C221")
      (value "0,01 мкФ")
      (footprint "CC0402(1005)")
      (description "Чип конденсатор керамический")
      (fields (field (name "Comment") "CC0402-X7R-0,01 мкФ-10%-50В"))
      (libsource (lib "Чип конденсаторы") (part "CC0402-X7R-#-20%-10В"))
    )
    (comp (ref "C222")
      (value "0,01 мкФ")
      (footprint "CC0402(1005)")
      (description "Чип конденсатор керамический")
      (fields (field (name "Comment") "CC0402-X7R-0,01 мкФ-10%-50В"))
      (libsource (lib "Чип конденсаторы") (part "CC0402-X7R-#-20%-10В"))
    )
    (comp (ref "C223")
      (value "0,1 мкФ")
      (footprint "CC0402(1005)")
      (description "Чип конденсатор керамический")
      (fields (field (name "Comment") "CC0402-X7R-0,1 мкФ-20%-10В"))
      (libsource (lib "Чип конденсаторы") (part "CC0402-X7R-#-20%-10В"))
    )
    (comp (ref "C224")
      (value "0,1 мкФ")
      (footprint "CC0402(1005)")
      (description "Чип конденсатор керамический")
      (fields (field (name "Comment") "CC0402-X7R-0,1 мкФ-20%-10В"))
      (libsource (lib "Чип конденсаторы") (part "CC0402-X7R-#-20%-10В"))
    )
    (comp (ref "C225")
      (value "0,1 мкФ")
      (footprint "CC0402(1005)")
      (description "Чип конденсатор керамический")
      (fields (field (name "Comment") "CC0402-X7R-0,1 мкФ-20%-10В"))
      (libsource (lib "Чип конденсаторы") (part "CC0402-X7R-#-20%-10В"))
    )
    (comp (ref "C226")
      (value "0,01 мкФ")
      (footprint "CC0402(1005)")
      (description "Чип конденсатор керамический")
      (fields (field (name "Comment") "CC0402-X7R-0,01 мкФ-10%-50В"))
      (libsource (lib "Чип конденсаторы") (part "CC0402-X7R-#-20%-10В"))
    )
    (comp (ref "C227")
      (value "4700 пФ")
      (footprint "CC0402(1005)")
      (description "Чип конденсатор керамический")
      (fields (field (name "Comment") "CC0402-X7R-4700 пФ-10%-50В"))
      (libsource (lib "Чип конденсаторы") (part "CC0402-X7R-#-20%-10В"))
    )
    (comp (ref "C228")
      (value "4700 пФ")
      (footprint "CC0402(1005)")
      (description "Чип конденсатор керамический")
      (fields (field (name "Comment") "CC0402-X7R-4700 пФ-10%-50В"))
      (libsource (lib "Чип конденсаторы") (part "CC0402-X7R-#-20%-10В"))
    )
    (comp (ref "C229")
      (value "0,22 мкФ")
      (footprint "CC0402(1005)")
      (description "Чип конденсатор керамический")
      (fields (field (name "Comment") "CC0402-X7R-0,22 мкФ-10%-6.3В"))
      (libsource (lib "Чип конденсаторы") (part "CC0402-X7R-#-20%-10В"))
    )
    (comp (ref "C230")
      (value "0,22 мкФ")
      (footprint "CC0402(1005)")
      (description "Чип конденсатор керамический")
      (fields (field (name "Comment") "CC0402-X7R-0,22 мкФ-10%-6.3В"))
      (libsource (lib "Чип конденсаторы") (part "CC0402-X7R-#-20%-10В"))
    )
    (comp (ref "C231")
      (value "0,47 мкФ")
      (footprint "CC0402(1005)")
      (description "Чип конденсатор керамический")
      (fields (field (name "Comment") "CC0402-X7R-0,47 мкФ-10%-6.3В"))
      (libsource (lib "Чип конденсаторы") (part "CC0402-X7R-#-20%-10В"))
    )
    (comp (ref "C232")
      (value "0,1 мкФ")
      (footprint "CC0402(1005)")
      (description "Чип конденсатор керамический")
      (fields (field (name "Comment") "CC0402-X7R-0,1 мкФ-20%-10В"))
      (libsource (lib "Чип конденсаторы") (part "CC0402-X7R-#-20%-10В"))
    )
    (comp (ref "C233")
      (value "0,1 мкФ")
      (footprint "CC0402(1005)")
      (description "Чип конденсатор керамический")
      (fields (field (name "Comment") "CC0402-X7R-0,1 мкФ-20%-10В"))
      (libsource (lib "Чип конденсаторы") (part "CC0402-X7R-#-20%-10В"))
    )
    (comp (ref "C234")
      (value "0,01 мкФ")
      (footprint "CC0402(1005)")
      (description "Чип конденсатор керамический")
      (fields (field (name "Comment") "CC0402-X7R-0,01 мкФ-10%-50В"))
      (libsource (lib "Чип конденсаторы") (part "CC0402-X7R-#-20%-10В"))
    )
    (comp (ref "C235")
      (value "0,01 мкФ")
      (footprint "CC0402(1005)")
      (description "Чип конденсатор керамический")
      (fields (field (name "Comment") "CC0402-X7R-0,01 мкФ-10%-50В"))
      (libsource (lib "Чип конденсаторы") (part "CC0402-X7R-#-20%-10В"))
    )
    (comp (ref "C236")
      (value "0,01 мкФ")
      (footprint "CC0402(1005)")
      (description "Чип конденсатор керамический")
      (fields (field (name "Comment") "CC0402-X7R-0,01 мкФ-10%-50В"))
      (libsource (lib "Чип конденсаторы") (part "CC0402-X7R-#-20%-10В"))
    )
    (comp (ref "C237")
      (value "0,01 мкФ")
      (footprint "CC0402(1005)")
      (description "Чип конденсатор керамический")
      (fields (field (name "Comment") "CC0402-X7R-0,01 мкФ-10%-50В"))
      (libsource (lib "Чип конденсаторы") (part "CC0402-X7R-#-20%-10В"))
    )
    (comp (ref "C238")
      (value "0,01 мкФ")
      (footprint "CC0402(1005)")
      (description "Чип конденсатор керамический")
      (fields (field (name "Comment") "CC0402-X7R-0,01 мкФ-10%-50В"))
      (libsource (lib "Чип конденсаторы") (part "CC0402-X7R-#-20%-10В"))
    )
    (comp (ref "C239")
      (value "0,1 мкФ")
      (footprint "CC0402(1005)")
      (description "Чип конденсатор керамический")
      (fields (field (name "Comment") "CC0402-X7R-0,1 мкФ-20%-10В"))
      (libsource (lib "Чип конденсаторы") (part "CC0402-X7R-#-20%-10В"))
    )
    (comp (ref "C240")
      (value "0,1 мкФ")
      (footprint "CC0402(1005)")
      (description "Чип конденсатор керамический")
      (fields (field (name "Comment") "CC0402-X7R-0,1 мкФ-20%-10В"))
      (libsource (lib "Чип конденсаторы") (part "CC0402-X7R-#-20%-10В"))
    )
    (comp (ref "C241")
      (value "0,1 мкФ")
      (footprint "CC0402(1005)")
      (description "Чип конденсатор керамический")
      (fields (field (name "Comment") "CC0402-X7R-0,1 мкФ-20%-10В"))
      (libsource (lib "Чип конденсаторы") (part "CC0402-X7R-#-20%-10В"))
    )
    (comp (ref "C242")
      (value "0,1 мкФ")
      (footprint "CC0402(1005)")
      (description "Чип конденсатор керамический")
      (fields (field (name "Comment") "CC0402-X7R-0,1 мкФ-20%-10В"))
      (libsource (lib "Чип конденсаторы") (part "CC0402-X7R-#-20%-10В"))
    )
    (comp (ref "C243")
      (value "0,1 мкФ")
      (footprint "CC0402(1005)")
      (description "Чип конденсатор керамический")
      (fields (field (name "Comment") "CC0402-X7R-0,1 мкФ-20%-10В"))
      (libsource (lib "Чип конденсаторы") (part "CC0402-X7R-#-20%-10В"))
    )
    (comp (ref "C244")
      (value "0,01 мкФ")
      (footprint "CC0402(1005)")
      (description "Чип конденсатор керамический")
      (fields (field (name "Comment") "CC0402-X7R-0,01 мкФ-10%-50В"))
      (libsource (lib "Чип конденсаторы") (part "CC0402-X7R-#-20%-10В"))
    )
    (comp (ref "C245")
      (value "0,01 мкФ")
      (footprint "CC0402(1005)")
      (description "Чип конденсатор керамический")
      (fields (field (name "Comment") "CC0402-X7R-0,01 мкФ-10%-50В"))
      (libsource (lib "Чип конденсаторы") (part "CC0402-X7R-#-20%-10В"))
    )
    (comp (ref "C246")
      (value "4700 пФ")
      (footprint "CC0402(1005)")
      (description "Чип конденсатор керамический")
      (fields (field (name "Comment") "CC0402-X7R-4700 пФ-10%-50В"))
      (libsource (lib "Чип конденсаторы") (part "CC0402-X7R-#-20%-10В"))
    )
    (comp (ref "C247")
      (value "4700 пФ")
      (footprint "CC0402(1005)")
      (description "Чип конденсатор керамический")
      (fields (field (name "Comment") "CC0402-X7R-4700 пФ-10%-50В"))
      (libsource (lib "Чип конденсаторы") (part "CC0402-X7R-#-20%-10В"))
    )
    (comp (ref "C248")
      (value "0,22 мкФ")
      (footprint "CC0402(1005)")
      (description "Чип конденсатор керамический")
      (fields (field (name "Comment") "CC0402-X7R-0,22 мкФ-10%-6.3В"))
      (libsource (lib "Чип конденсаторы") (part "CC0402-X7R-#-20%-10В"))
    )
    (comp (ref "C249")
      (value "0,22 мкФ")
      (footprint "CC0402(1005)")
      (description "Чип конденсатор керамический")
      (fields (field (name "Comment") "CC0402-X7R-0,22 мкФ-10%-6.3В"))
      (libsource (lib "Чип конденсаторы") (part "CC0402-X7R-#-20%-10В"))
    )
    (comp (ref "C250")
      (value "0,47 мкФ")
      (footprint "CC0402(1005)")
      (description "Чип конденсатор керамический")
      (fields (field (name "Comment") "CC0402-X7R-0,47 мкФ-10%-6.3В"))
      (libsource (lib "Чип конденсаторы") (part "CC0402-X7R-#-20%-10В"))
    )
    (comp (ref "C251")
      (value "0,1 мкФ")
      (footprint "CC0402(1005)")
      (description "Чип конденсатор керамический")
      (fields (field (name "Comment") "CC0402-X7R-0,1 мкФ-20%-10В"))
      (libsource (lib "Чип конденсаторы") (part "CC0402-X7R-#-20%-10В"))
    )
    (comp (ref "C252")
      (value "0,1 мкФ")
      (footprint "CC0402(1005)")
      (description "Чип конденсатор керамический")
      (fields (field (name "Comment") "CC0402-X7R-0,1 мкФ-20%-10В"))
      (libsource (lib "Чип конденсаторы") (part "CC0402-X7R-#-20%-10В"))
    )
    (comp (ref "C253")
      (value "0,1 мкФ")
      (footprint "CC0402(1005)")
      (description "Чип конденсатор керамический")
      (fields (field (name "Comment") "CC0402-X7R-0,1 мкФ-20%-10В"))
      (libsource (lib "Чип конденсаторы") (part "CC0402-X7R-#-20%-10В"))
    )
    (comp (ref "C254")
      (value "0,22 мкФ")
      (footprint "CC0402(1005)")
      (description "Чип конденсатор керамический")
      (fields (field (name "Comment") "CC0402-X7R-0,22 мкФ-10%-6.3В"))
      (libsource (lib "Чип конденсаторы") (part "CC0402-X7R-#-20%-10В"))
    )
    (comp (ref "C255")
      (value "0,01 мкФ")
      (footprint "CC0402(1005)")
      (description "Чип конденсатор керамический")
      (fields (field (name "Comment") "CC0402-X7R-0,01 мкФ-10%-50В"))
      (libsource (lib "Чип конденсаторы") (part "CC0402-X7R-#-20%-10В"))
    )
    (comp (ref "C256")
      (value "0,01 мкФ")
      (footprint "CC0402(1005)")
      (description "Чип конденсатор керамический")
      (fields (field (name "Comment") "CC0402-X7R-0,01 мкФ-10%-50В"))
      (libsource (lib "Чип конденсаторы") (part "CC0402-X7R-#-20%-10В"))
    )
    (comp (ref "C257")
      (value "0,01 мкФ")
      (footprint "CC0402(1005)")
      (description "Чип конденсатор керамический")
      (fields (field (name "Comment") "CC0402-X7R-0,01 мкФ-10%-50В"))
      (libsource (lib "Чип конденсаторы") (part "CC0402-X7R-#-20%-10В"))
    )
    (comp (ref "C258")
      (value "0,01 мкФ")
      (footprint "CC0402(1005)")
      (description "Чип конденсатор керамический")
      (fields (field (name "Comment") "CC0402-X7R-0,01 мкФ-10%-50В"))
      (libsource (lib "Чип конденсаторы") (part "CC0402-X7R-#-20%-10В"))
    )
    (comp (ref "C259")
      (value "0,1 мкФ")
      (footprint "CC0402(1005)")
      (description "Чип конденсатор керамический")
      (fields (field (name "Comment") "CC0402-X7R-0,1 мкФ-20%-10В"))
      (libsource (lib "Чип конденсаторы") (part "CC0402-X7R-#-20%-10В"))
    )
    (comp (ref "C260")
      (value "0,1 мкФ")
      (footprint "CC0402(1005)")
      (description "Чип конденсатор керамический")
      (fields (field (name "Comment") "CC0402-X7R-0,1 мкФ-20%-10В"))
      (libsource (lib "Чип конденсаторы") (part "CC0402-X7R-#-20%-10В"))
    )
    (comp (ref "C261")
      (value "0,1 мкФ")
      (footprint "CC0402(1005)")
      (description "Чип конденсатор керамический")
      (fields (field (name "Comment") "CC0402-X7R-0,1 мкФ-20%-10В"))
      (libsource (lib "Чип конденсаторы") (part "CC0402-X7R-#-20%-10В"))
    )
    (comp (ref "C262")
      (value "0,22 мкФ")
      (footprint "CC0402(1005)")
      (description "Чип конденсатор керамический")
      (fields (field (name "Comment") "CC0402-X7R-0,22 мкФ-10%-6.3В"))
      (libsource (lib "Чип конденсаторы") (part "CC0402-X7R-#-20%-10В"))
    )
    (comp (ref "C263")
      (value "0,01 мкФ")
      (footprint "CC0402(1005)")
      (description "Чип конденсатор керамический")
      (fields (field (name "Comment") "CC0402-X7R-0,01 мкФ-10%-50В"))
      (libsource (lib "Чип конденсаторы") (part "CC0402-X7R-#-20%-10В"))
    )
    (comp (ref "C264")
      (value "0,01 мкФ")
      (footprint "CC0402(1005)")
      (description "Чип конденсатор керамический")
      (fields (field (name "Comment") "CC0402-X7R-0,01 мкФ-10%-50В"))
      (libsource (lib "Чип конденсаторы") (part "CC0402-X7R-#-20%-10В"))
    )
    (comp (ref "C265")
      (value "0,01 мкФ")
      (footprint "CC0402(1005)")
      (description "Чип конденсатор керамический")
      (fields (field (name "Comment") "CC0402-X7R-0,01 мкФ-10%-50В"))
      (libsource (lib "Чип конденсаторы") (part "CC0402-X7R-#-20%-10В"))
    )
    (comp (ref "C266")
      (value "0,01 мкФ")
      (footprint "CC0402(1005)")
      (description "Чип конденсатор керамический")
      (fields (field (name "Comment") "CC0402-X7R-0,01 мкФ-10%-50В"))
      (libsource (lib "Чип конденсаторы") (part "CC0402-X7R-#-20%-10В"))
    )
    (comp (ref "C271")
      (value "10 мкФ")
      (footprint "CC0402(1005)")
      (description "Чип конденсатор керамический")
      (fields (field (name "Comment") "CC0402-X5R-10 мкФ-20%-6.3В"))
      (libsource (lib "Чип конденсаторы") (part "CC0402-X7R-#-20%-10В"))
    )
    (comp (ref "C272")
      (value "10 мкФ")
      (footprint "CC0402(1005)")
      (description "Чип конденсатор керамический")
      (fields (field (name "Comment") "CC0402-X5R-10 мкФ-20%-6.3В"))
      (libsource (lib "Чип конденсаторы") (part "CC0402-X7R-#-20%-10В"))
    )
    (comp (ref "C273")
      (value "10 мкФ")
      (footprint "CC0402(1005)")
      (description "Чип конденсатор керамический")
      (fields (field (name "Comment") "CC0402-X5R-10 мкФ-20%-6.3В"))
      (libsource (lib "Чип конденсаторы") (part "CC0402-X7R-#-20%-10В"))
    )
    (comp (ref "C274")
      (value "0,01 мкФ")
      (footprint "CC0402(1005)")
      (description "Чип конденсатор керамический")
      (fields (field (name "Comment") "CC0402-X7R-0,01 мкФ-10%-50В"))
      (libsource (lib "Чип конденсаторы") (part "CC0402-X7R-#-20%-10В"))
    )
    (comp (ref "C275")
      (value "0,1 мкФ")
      (footprint "CC0402(1005)")
      (description "Чип конденсатор керамический")
      (fields (field (name "Comment") "CC0402-X7R-0,1 мкФ-20%-10В"))
      (libsource (lib "Чип конденсаторы") (part "CC0402-X7R-#-20%-10В"))
    )
    (comp (ref "C276")
      (value "0,01 мкФ")
      (footprint "CC0402(1005)")
      (description "Чип конденсатор керамический")
      (fields (field (name "Comment") "CC0402-X7R-0,01 мкФ-10%-50В"))
      (libsource (lib "Чип конденсаторы") (part "CC0402-X7R-#-20%-10В"))
    )
    (comp (ref "C277")
      (value "0,1 мкФ")
      (footprint "CC0402(1005)")
      (description "Чип конденсатор керамический")
      (fields (field (name "Comment") "CC0402-X7R-0,1 мкФ-20%-10В"))
      (libsource (lib "Чип конденсаторы") (part "CC0402-X7R-#-20%-10В"))
    )
    (comp (ref "C278")
      (value "10 мкФ")
      (footprint "CC0402(1005)")
      (description "Чип конденсатор керамический")
      (fields (field (name "Comment") "CC0402-X5R-10 мкФ-20%-6.3В"))
      (libsource (lib "Чип конденсаторы") (part "CC0402-X7R-#-20%-10В"))
    )
    (comp (ref "C279")
      (value "0,01 мкФ")
      (footprint "CC0402(1005)")
      (description "Чип конденсатор керамический")
      (fields (field (name "Comment") "CC0402-X7R-0,01 мкФ-10%-50В"))
      (libsource (lib "Чип конденсаторы") (part "CC0402-X7R-#-20%-10В"))
    )
    (comp (ref "C280")
      (value "0,1 мкФ")
      (footprint "CC0402(1005)")
      (description "Чип конденсатор керамический")
      (fields (field (name "Comment") "CC0402-X7R-0,1 мкФ-20%-10В"))
      (libsource (lib "Чип конденсаторы") (part "CC0402-X7R-#-20%-10В"))
    )
    (comp (ref "C281")
      (value "0,01 мкФ")
      (footprint "CC0402(1005)")
      (description "Чип конденсатор керамический")
      (fields (field (name "Comment") "CC0402-X7R-0,01 мкФ-10%-50В"))
      (libsource (lib "Чип конденсаторы") (part "CC0402-X7R-#-20%-10В"))
    )
    (comp (ref "C282")
      (value "0,1 мкФ")
      (footprint "CC0402(1005)")
      (description "Чип конденсатор керамический")
      (fields (field (name "Comment") "CC0402-X7R-0,1 мкФ-20%-10В"))
      (libsource (lib "Чип конденсаторы") (part "CC0402-X7R-#-20%-10В"))
    )
    (comp (ref "D2")
      (value "5CSXFC6D6F31I7N")
      (footprint "ALTR-FBGA896_A-200")
      (fields (field (name "MANUFACTURER") "Altera"))
      (libsource (lib "") (part "5CSXFC6D6F31I7N_1"))
    )
    (comp (ref "L1")
      (value "MH1608-600Y")
      (footprint "CL0805")
      (description "Чип индуктивность подавления EMP")
      (libsource (lib "Индуктивности") (part "BLM21"))
    )
    (comp (ref "L2")
      (value "MH1608-600Y")
      (footprint "CL0805")
      (description "Чип индуктивность подавления EMP")
      (libsource (lib "Индуктивности") (part "BLM21"))
    )
    (comp (ref "L3")
      (value "BLM18PG-60 Ом")
      (footprint "CL0603")
      (description "Чип индуктивность подавления EMP")
      (libsource (lib "Индуктивности") (part "BLM18"))
    )
    (comp (ref "L4")
      (value "BLM18PG-60 Ом")
      (footprint "CL0603")
      (description "Чип индуктивность подавления EMP")
      (libsource (lib "Индуктивности") (part "BLM18"))
    )
    (comp (ref "L5")
      (value "BLM18PG-60 Ом")
      (footprint "CL0603")
      (description "Чип индуктивность подавления EMP")
      (libsource (lib "Индуктивности") (part "BLM18"))
    )
    (comp (ref "L6")
      (value "BLM18PG-60 Ом")
      (footprint "CL0603")
      (description "Чип индуктивность подавления EMP")
      (libsource (lib "Индуктивности") (part "BLM18"))
    )
    (comp (ref "L13")
      (value "BLM18PG-60 Ом")
      (footprint "CL0603")
      (description "Чип индуктивность подавления EMP")
      (libsource (lib "Индуктивности") (part "BLM18"))
    )
  )
  (nets
    (net (code "1") (name "DDR3_VREF_FPGA") (class "Default")
      (node (ref "C167") (pin "1") (pinfunction "+_1") (pintype "passive"))
      (node (ref "D2") (pin "AJ15") (pinfunction "VREFB3BN0_AJ15") (pintype "power_in"))
      (node (ref "D2") (pin "AK17") (pinfunction "VREFB4AN0_AK17") (pintype "power_in"))
    )
    (net (code "2") (name "DDR3_VREF_HPS") (class "Default")
      (node (ref "D2") (pin "G27") (pinfunction "VREFB6AN0_HPS_G27") (pintype "power_in"))
      (node (ref "D2") (pin "U30") (pinfunction "VREFB6BN0_HPS_U30") (pintype "power_in"))
    )
    (net (code "3") (name "GND") (class "Default")
      (node (ref "C103") (pin "1") (pinfunction "+_1") (pintype "passive"))
      (node (ref "C105") (pin "1") (pinfunction "+_1") (pintype "passive"))
      (node (ref "C106") (pin "1") (pinfunction "+_1") (pintype "passive"))
      (node (ref "C107") (pin "1") (pinfunction "+_1") (pintype "passive"))
      (node (ref "C108") (pin "1") (pinfunction "+_1") (pintype "passive"))
      (node (ref "C109") (pin "1") (pinfunction "+_1") (pintype "passive"))
      (node (ref "C110") (pin "1") (pinfunction "+_1") (pintype "passive"))
      (node (ref "C111") (pin "1") (pinfunction "+_1") (pintype "passive"))
      (node (ref "C112") (pin "2") (pinfunction "-_2") (pintype "passive"))
      (node (ref "C113") (pin "1") (pinfunction "+_1") (pintype "passive"))
      (node (ref "C114") (pin "1") (pinfunction "+_1") (pintype "passive"))
      (node (ref "C115") (pin "1") (pinfunction "+_1") (pintype "passive"))
      (node (ref "C116") (pin "1") (pinfunction "+_1") (pintype "passive"))
      (node (ref "C117") (pin "1") (pinfunction "+_1") (pintype "passive"))
      (node (ref "C118") (pin "1") (pinfunction "+_1") (pintype "passive"))
      (node (ref "C119") (pin "1") (pinfunction "+_1") (pintype "passive"))
      (node (ref "C120") (pin "1") (pinfunction "+_1") (pintype "passive"))
      (node (ref "C121") (pin "1") (pinfunction "+_1") (pintype "passive"))
      (node (ref "C122") (pin "1") (pinfunction "+_1") (pintype "passive"))
      (node (ref "C123") (pin "1") (pinfunction "+_1") (pintype "passive"))
      (node (ref "C124") (pin "1") (pinfunction "+_1") (pintype "passive"))
      (node (ref "C125") (pin "1") (pinfunction "+_1") (pintype "passive"))
      (node (ref "C126") (pin "1") (pinfunction "+_1") (pintype "passive"))
      (node (ref "C127") (pin "1") (pinfunction "+_1") (pintype "passive"))
      (node (ref "C128") (pin "1") (pinfunction "+_1") (pintype "passive"))
      (node (ref "C129") (pin "1") (pinfunction "+_1") (pintype "passive"))
      (node (ref "C130") (pin "1") (pinfunction "+_1") (pintype "passive"))
      (node (ref "C131") (pin "1") (pinfunction "+_1") (pintype "passive"))
      (node (ref "C132") (pin "1") (pinfunction "+_1") (pintype "passive"))
      (node (ref "C133") (pin "1") (pinfunction "+_1") (pintype "passive"))
      (node (ref "C134") (pin "1") (pinfunction "+_1") (pintype "passive"))
      (node (ref "C135") (pin "1") (pinfunction "+_1") (pintype "passive"))
      (node (ref "C136") (pin "1") (pinfunction "+_1") (pintype "passive"))
      (node (ref "C137") (pin "2") (pinfunction "-_2") (pintype "passive"))
      (node (ref "C138") (pin "1") (pinfunction "+_1") (pintype "passive"))
      (node (ref "C139") (pin "1") (pinfunction "+_1") (pintype "passive"))
      (node (ref "C140") (pin "1") (pinfunction "+_1") (pintype "passive"))
      (node (ref "C141") (pin "1") (pinfunction "+_1") (pintype "passive"))
      (node (ref "C142") (pin "1") (pinfunction "+_1") (pintype "passive"))
      (node (ref "C143") (pin "1") (pinfunction "+_1") (pintype "passive"))
      (node (ref "C144") (pin "1") (pinfunction "+_1") (pintype "passive"))
      (node (ref "C145") (pin "1") (pinfunction "+_1") (pintype "passive"))
      (node (ref "C146") (pin "1") (pinfunction "+_1") (pintype "passive"))
      (node (ref "C147") (pin "1") (pinfunction "+_1") (pintype "passive"))
      (node (ref "C148") (pin "1") (pinfunction "+_1") (pintype "passive"))
      (node (ref "C149") (pin "1") (pinfunction "+_1") (pintype "passive"))
      (node (ref "C150") (pin "1") (pinfunction "+_1") (pintype "passive"))
      (node (ref "C151") (pin "1") (pinfunction "+_1") (pintype "passive"))
      (node (ref "C152") (pin "1") (pinfunction "+_1") (pintype "passive"))
      (node (ref "C153") (pin "1") (pinfunction "+_1") (pintype "passive"))
      (node (ref "C154") (pin "2") (pinfunction "-_2") (pintype "passive"))
      (node (ref "C155") (pin "1") (pinfunction "+_1") (pintype "passive"))
      (node (ref "C156") (pin "1") (pinfunction "+_1") (pintype "passive"))
      (node (ref "C157") (pin "1") (pinfunction "+_1") (pintype "passive"))
      (node (ref "C158") (pin "1") (pinfunction "+_1") (pintype "passive"))
      (node (ref "C159") (pin "1") (pinfunction "+_1") (pintype "passive"))
      (node (ref "C160") (pin "1") (pinfunction "+_1") (pintype "passive"))
      (node (ref "C161") (pin "1") (pinfunction "+_1") (pintype "passive"))
      (node (ref "C162") (pin "2") (pinfunction "-_2") (pintype "passive"))
      (node (ref "C163") (pin "2") (pinfunction "-_2") (pintype "passive"))
      (node (ref "C164") (pin "1") (pinfunction "+_1") (pintype "passive"))
      (node (ref "C165") (pin "1") (pinfunction "+_1") (pintype "passive"))
      (node (ref "C166") (pin "1") (pinfunction "+_1") (pintype "passive"))
      (node (ref "C167") (pin "2") (pinfunction "-_2") (pintype "passive"))
      (node (ref "C168") (pin "2") (pinfunction "-_2") (pintype "passive"))
      (node (ref "C169") (pin "2") (pinfunction "-_2") (pintype "passive"))
      (node (ref "C170") (pin "2") (pinfunction "-_2") (pintype "passive"))
      (node (ref "C171") (pin "2") (pinfunction "-_2") (pintype "passive"))
      (node (ref "C172") (pin "2") (pinfunction "-_2") (pintype "passive"))
      (node (ref "C173") (pin "2") (pinfunction "-_2") (pintype "passive"))
      (node (ref "C174") (pin "2") (pinfunction "-_2") (pintype "passive"))
      (node (ref "C175") (pin "2") (pinfunction "-_2") (pintype "passive"))
      (node (ref "C176") (pin "1") (pinfunction "+_1") (pintype "passive"))
      (node (ref "C177") (pin "1") (pinfunction "+_1") (pintype "passive"))
      (node (ref "C178") (pin "1") (pinfunction "+_1") (pintype "passive"))
      (node (ref "C179") (pin "1") (pinfunction "+_1") (pintype "passive"))
      (node (ref "C180") (pin "2") (pinfunction "-_2") (pintype "passive"))
      (node (ref "C181") (pin "2") (pinfunction "-_2") (pintype "passive"))
      (node (ref "C182") (pin "2") (pinfunction "-_2") (pintype "passive"))
      (node (ref "C183") (pin "2") (pinfunction "-_2") (pintype "passive"))
      (node (ref "C184") (pin "2") (pinfunction "-_2") (pintype "passive"))
      (node (ref "C185") (pin "2") (pinfunction "-_2") (pintype "passive"))
      (node (ref "C186") (pin "2") (pinfunction "-_2") (pintype "passive"))
      (node (ref "C187") (pin "2") (pinfunction "-_2") (pintype "passive"))
      (node (ref "C188") (pin "2") (pinfunction "-_2") (pintype "passive"))
      (node (ref "C189") (pin "2") (pinfunction "-_2") (pintype "passive"))
      (node (ref "C190") (pin "2") (pinfunction "-_2") (pintype "passive"))
      (node (ref "C191") (pin "2") (pinfunction "-_2") (pintype "passive"))
      (node (ref "C192") (pin "2") (pinfunction "-_2") (pintype "passive"))
      (node (ref "C193") (pin "2") (pinfunction "-_2") (pintype "passive"))
      (node (ref "C194") (pin "1") (pinfunction "+_1") (pintype "passive"))
      (node (ref "C195") (pin "1") (pinfunction "+_1") (pintype "passive"))
      (node (ref "C196") (pin "1") (pinfunction "+_1") (pintype "passive"))
      (node (ref "C197") (pin "1") (pinfunction "+_1") (pintype "passive"))
      (node (ref "C198") (pin "1") (pinfunction "+_1") (pintype "passive"))
      (node (ref "C199") (pin "1") (pinfunction "+_1") (pintype "passive"))
      (node (ref "C200") (pin "1") (pinfunction "+_1") (pintype "passive"))
      (node (ref "C201") (pin "1") (pinfunction "+_1") (pintype "passive"))
      (node (ref "C202") (pin "2") (pinfunction "-_2") (pintype "passive"))
      (node (ref "C203") (pin "2") (pinfunction "-_2") (pintype "passive"))
      (node (ref "C204") (pin "2") (pinfunction "-_2") (pintype "passive"))
      (node (ref "C205") (pin "2") (pinfunction "-_2") (pintype "passive"))
      (node (ref "C206") (pin "1") (pinfunction "+_1") (pintype "passive"))
      (node (ref "C207") (pin "1") (pinfunction "+_1") (pintype "passive"))
      (node (ref "C208") (pin "1") (pinfunction "+_1") (pintype "passive"))
      (node (ref "C209") (pin "1") (pinfunction "+_1") (pintype "passive"))
      (node (ref "C210") (pin "1") (pinfunction "+_1") (pintype "passive"))
      (node (ref "C211") (pin "1") (pinfunction "+_1") (pintype "passive"))
      (node (ref "C212") (pin "1") (pinfunction "+_1") (pintype "passive"))
      (node (ref "C213") (pin "1") (pinfunction "+_1") (pintype "passive"))
      (node (ref "C214") (pin "1") (pinfunction "+_1") (pintype "passive"))
      (node (ref "C215") (pin "1") (pinfunction "+_1") (pintype "passive"))
      (node (ref "C216") (pin "1") (pinfunction "+_1") (pintype "passive"))
      (node (ref "C217") (pin "1") (pinfunction "+_1") (pintype "passive"))
      (node (ref "C218") (pin "1") (pinfunction "+_1") (pintype "passive"))
      (node (ref "C219") (pin "1") (pinfunction "+_1") (pintype "passive"))
      (node (ref "C220") (pin "1") (pinfunction "+_1") (pintype "passive"))
      (node (ref "C221") (pin "1") (pinfunction "+_1") (pintype "passive"))
      (node (ref "C222") (pin "1") (pinfunction "+_1") (pintype "passive"))
      (node (ref "C223") (pin "1") (pinfunction "+_1") (pintype "passive"))
      (node (ref "C224") (pin "1") (pinfunction "+_1") (pintype "passive"))
      (node (ref "C225") (pin "1") (pinfunction "+_1") (pintype "passive"))
      (node (ref "C226") (pin "1") (pinfunction "+_1") (pintype "passive"))
      (node (ref "C227") (pin "2") (pinfunction "-_2") (pintype "passive"))
      (node (ref "C228") (pin "2") (pinfunction "-_2") (pintype "passive"))
      (node (ref "C229") (pin "1") (pinfunction "+_1") (pintype "passive"))
      (node (ref "C230") (pin "1") (pinfunction "+_1") (pintype "passive"))
      (node (ref "C231") (pin "1") (pinfunction "+_1") (pintype "passive"))
      (node (ref "C232") (pin "1") (pinfunction "+_1") (pintype "passive"))
      (node (ref "C233") (pin "1") (pinfunction "+_1") (pintype "passive"))
      (node (ref "C234") (pin "1") (pinfunction "+_1") (pintype "passive"))
      (node (ref "C235") (pin "1") (pinfunction "+_1") (pintype "passive"))
      (node (ref "C236") (pin "1") (pinfunction "+_1") (pintype "passive"))
      (node (ref "C237") (pin "1") (pinfunction "+_1") (pintype "passive"))
      (node (ref "C238") (pin "1") (pinfunction "+_1") (pintype "passive"))
      (node (ref "C239") (pin "1") (pinfunction "+_1") (pintype "passive"))
      (node (ref "C240") (pin "1") (pinfunction "+_1") (pintype "passive"))
      (node (ref "C241") (pin "1") (pinfunction "+_1") (pintype "passive"))
      (node (ref "C242") (pin "1") (pinfunction "+_1") (pintype "passive"))
      (node (ref "C243") (pin "1") (pinfunction "+_1") (pintype "passive"))
      (node (ref "C244") (pin "1") (pinfunction "+_1") (pintype "passive"))
      (node (ref "C245") (pin "1") (pinfunction "+_1") (pintype "passive"))
      (node (ref "C246") (pin "2") (pinfunction "-_2") (pintype "passive"))
      (node (ref "C247") (pin "2") (pinfunction "-_2") (pintype "passive"))
      (node (ref "C248") (pin "1") (pinfunction "+_1") (pintype "passive"))
      (node (ref "C249") (pin "1") (pinfunction "+_1") (pintype "passive"))
      (node (ref "C250") (pin "1") (pinfunction "+_1") (pintype "passive"))
      (node (ref "C251") (pin "1") (pinfunction "+_1") (pintype "passive"))
      (node (ref "C252") (pin "1") (pinfunction "+_1") (pintype "passive"))
      (node (ref "C253") (pin "1") (pinfunction "+_1") (pintype "passive"))
      (node (ref "C254") (pin "1") (pinfunction "+_1") (pintype "passive"))
      (node (ref "C255") (pin "1") (pinfunction "+_1") (pintype "passive"))
      (node (ref "C256") (pin "1") (pinfunction "+_1") (pintype "passive"))
      (node (ref "C257") (pin "1") (pinfunction "+_1") (pintype "passive"))
      (node (ref "C258") (pin "1") (pinfunction "+_1") (pintype "passive"))
      (node (ref "C259") (pin "1") (pinfunction "+_1") (pintype "passive"))
      (node (ref "C260") (pin "1") (pinfunction "+_1") (pintype "passive"))
      (node (ref "C261") (pin "1") (pinfunction "+_1") (pintype "passive"))
      (node (ref "C262") (pin "1") (pinfunction "+_1") (pintype "passive"))
      (node (ref "C263") (pin "1") (pinfunction "+_1") (pintype "passive"))
      (node (ref "C264") (pin "1") (pinfunction "+_1") (pintype "passive"))
      (node (ref "C265") (pin "1") (pinfunction "+_1") (pintype "passive"))
      (node (ref "C266") (pin "1") (pinfunction "+_1") (pintype "passive"))
      (node (ref "C271") (pin "1") (pinfunction "+_1") (pintype "passive"))
      (node (ref "C272") (pin "1") (pinfunction "+_1") (pintype "passive"))
      (node (ref "C273") (pin "2") (pinfunction "-_2") (pintype "passive"))
      (node (ref "C274") (pin "2") (pinfunction "-_2") (pintype "passive"))
      (node (ref "C275") (pin "2") (pinfunction "-_2") (pintype "passive"))
      (node (ref "C276") (pin "2") (pinfunction "-_2") (pintype "passive"))
      (node (ref "C277") (pin "2") (pinfunction "-_2") (pintype "passive"))
      (node (ref "C278") (pin "2") (pinfunction "-_2") (pintype "passive"))
      (node (ref "C279") (pin "2") (pinfunction "-_2") (pintype "passive"))
      (node (ref "C280") (pin "2") (pinfunction "-_2") (pintype "passive"))
      (node (ref "C281") (pin "2") (pinfunction "-_2") (pintype "passive"))
      (node (ref "C282") (pin "2") (pinfunction "-_2") (pintype "passive"))
      (node (ref "C70") (pin "1") (pinfunction "+_1") (pintype "passive"))
      (node (ref "C87") (pin "2") (pinfunction "-_2") (pintype "passive"))
      (node (ref "C94") (pin "2") (pinfunction "-_2") (pintype "passive"))
      (node (ref "D2") (pin "A12") (pinfunction "GND_A12") (pintype "power_in"))
      (node (ref "D2") (pin "A17") (pinfunction "GND_A17") (pintype "power_in"))
      (node (ref "D2") (pin "A2") (pinfunction "GND_A2") (pintype "power_in"))
      (node (ref "D2") (pin "A22") (pinfunction "GND_A22") (pintype "power_in"))
      (node (ref "D2") (pin "A26") (pinfunction "GND_A26") (pintype "power_in"))
      (node (ref "D2") (pin "A27") (pinfunction "GND_A27") (pintype "power_in"))
      (node (ref "D2") (pin "AA11") (pinfunction "GND_AA11") (pintype "power_in"))
      (node (ref "D2") (pin "AA22") (pinfunction "GND_AA22") (pintype "power_in"))
      (node (ref "D2") (pin "AA29") (pinfunction "VREFB5BN0_AA29") (pintype "power_in"))
      (node (ref "D2") (pin "AA3") (pinfunction "GND_AA3") (pintype "power_in"))
      (node (ref "D2") (pin "AA4") (pinfunction "GND_AA4") (pintype "power_in"))
      (node (ref "D2") (pin "AA6") (pinfunction "GND_AA6") (pintype "power_in"))
      (node (ref "D2") (pin "AA9") (pinfunction "GND_AA9") (pintype "power_in"))
      (node (ref "D2") (pin "AB1") (pinfunction "GND_AB1") (pintype "power_in"))
      (node (ref "D2") (pin "AB19") (pinfunction "GND_AB19") (pintype "power_in"))
      (node (ref "D2") (pin "AB2") (pinfunction "GND_AB2") (pintype "power_in"))
      (node (ref "D2") (pin "AB29") (pinfunction "GND_AB29") (pintype "power_in"))
      (node (ref "D2") (pin "AB5") (pinfunction "GND_AB5") (pintype "power_in"))
      (node (ref "D2") (pin "AB7") (pinfunction "GND_AB7") (pintype "power_in"))
      (node (ref "D2") (pin "AC16") (pinfunction "GND_AC16") (pintype "power_in"))
      (node (ref "D2") (pin "AC24") (pinfunction "VREFB5AN0_AC24") (pintype "power_in"))
      (node (ref "D2") (pin "AC26") (pinfunction "GND_AC26") (pintype "power_in"))
      (node (ref "D2") (pin "AC3") (pinfunction "GND_AC3") (pintype "power_in"))
      (node (ref "D2") (pin "AC4") (pinfunction "GND_AC4") (pintype "power_in"))
      (node (ref "D2") (pin "AC6") (pinfunction "GND_AC6") (pintype "power_in"))
      (node (ref "D2") (pin "AC8") (pinfunction "GND_AC8") (pintype "power_in"))
      (node (ref "D2") (pin "AD1") (pinfunction "GND_AD1") (pintype "power_in"))
      (node (ref "D2") (pin "AD2") (pinfunction "GND_AD2") (pintype "power_in"))
      (node (ref "D2") (pin "AD23") (pinfunction "GND_AD23") (pintype "power_in"))
      (node (ref "D2") (pin "AD5") (pinfunction "GND_AD5") (pintype "power_in"))
      (node (ref "D2") (pin "AD6") (pinfunction "VREFB3AN0_AD6") (pintype "power_in"))
      (node (ref "D2") (pin "AE10") (pinfunction "GND_AE10") (pintype "power_in"))
      (node (ref "D2") (pin "AE20") (pinfunction "GND_AE20") (pintype "power_in"))
      (node (ref "D2") (pin "AE3") (pinfunction "GND_AE3") (pintype "power_in"))
      (node (ref "D2") (pin "AE4") (pinfunction "GND_AE4") (pintype "power_in"))
      (node (ref "D2") (pin "AF1") (pinfunction "GND_AF1") (pintype "power_in"))
      (node (ref "D2") (pin "AF12") (pinfunction "GND_AF12") (pintype "power_in"))
      (node (ref "D2") (pin "AF17") (pinfunction "GND_AF17") (pintype "power_in"))
      (node (ref "D2") (pin "AF2") (pinfunction "GND_AF2") (pintype "power_in"))
      (node (ref "D2") (pin "AF27") (pinfunction "GND_AF27") (pintype "power_in"))
      (node (ref "D2") (pin "AF3") (pinfunction "GND_AF3") (pintype "power_in"))
      (node (ref "D2") (pin "AG14") (pinfunction "GND_AG14") (pintype "power_in"))
      (node (ref "D2") (pin "AG24") (pinfunction "GND_AG24") (pintype "power_in"))
      (node (ref "D2") (pin "AG9") (pinfunction "GND_AG9") (pintype "power_in"))
      (node (ref "D2") (pin "AH1") (pinfunction "GND_AH1") (pintype "power_in"))
      (node (ref "D2") (pin "AH11") (pinfunction "GND_AH11") (pintype "power_in"))
      (node (ref "D2") (pin "AH21") (pinfunction "GND_AH21") (pintype "power_in"))
      (node (ref "D2") (pin "AH6") (pinfunction "GND_AH6") (pintype "power_in"))
      (node (ref "D2") (pin "AJ18") (pinfunction "GND_AJ18") (pintype "power_in"))
      (node (ref "D2") (pin "AJ28") (pinfunction "GND_AJ28") (pintype "power_in"))
      (node (ref "D2") (pin "AJ3") (pinfunction "GND_AJ3") (pintype "power_in"))
      (node (ref "D2") (pin "AJ30") (pinfunction "GND_AJ30") (pintype "power_in"))
      (node (ref "D2") (pin "AK15") (pinfunction "GND_AK15") (pintype "power_in"))
      (node (ref "D2") (pin "AK25") (pinfunction "GND_AK25") (pintype "power_in"))
      (node (ref "D2") (pin "AK5") (pinfunction "GND_AK5") (pintype "power_in"))
      (node (ref "D2") (pin "B10") (pinfunction "VREFB8AN0_B10") (pintype "power_in"))
      (node (ref "D2") (pin "B14") (pinfunction "GND_B14") (pintype "power_in"))
      (node (ref "D2") (pin "B19") (pinfunction "GND_B19") (pintype "power_in"))
      (node (ref "D2") (pin "B24") (pinfunction "GND_B24") (pintype "power_in"))
      (node (ref "D2") (pin "B29") (pinfunction "GND_B29") (pintype "power_in"))
      (node (ref "D2") (pin "B9") (pinfunction "GND_B9") (pintype "power_in"))
      (node (ref "D2") (pin "C1") (pinfunction "GND_C1") (pintype "power_in"))
      (node (ref "D2") (pin "C16") (pinfunction "GND_C16") (pintype "power_in"))
      (node (ref "D2") (pin "C21") (pinfunction "GND_C21") (pintype "power_in"))
      (node (ref "D2") (pin "C26") (pinfunction "GND_C26") (pintype "power_in"))
      (node (ref "D2") (pin "C6") (pinfunction "GND_C6") (pintype "power_in"))
      (node (ref "D2") (pin "D13") (pinfunction "GND_D13") (pintype "power_in"))
      (node (ref "D2") (pin "D23") (pinfunction "GND_D23") (pintype "power_in"))
      (node (ref "D2") (pin "D26") (pinfunction "GND_D26") (pintype "power_in"))
      (node (ref "D2") (pin "D3") (pinfunction "GND_D3") (pintype "power_in"))
      (node (ref "D2") (pin "E10") (pinfunction "GND_E10") (pintype "power_in"))
      (node (ref "D2") (pin "E22") (pinfunction "VREFB7A7B7C7DN0_HPS_E22") (pintype "power_in"))
      (node (ref "D2") (pin "E25") (pinfunction "GND_E25") (pintype "power_in"))
      (node (ref "D2") (pin "E30") (pinfunction "GND_E30") (pintype "power_in"))
      (node (ref "D2") (pin "F17") (pinfunction "GND_F17") (pintype "power_in"))
      (node (ref "D2") (pin "F2") (pinfunction "GND_F2") (pintype "power_in"))
      (node (ref "D2") (pin "F27") (pinfunction "GND_F27") (pintype "power_in"))
      (node (ref "D2") (pin "F5") (pinfunction "GND_F5") (pintype "power_in"))
      (node (ref "D2") (pin "F7") (pinfunction "GND_F7") (pintype "power_in"))
      (node (ref "D2") (pin "G24") (pinfunction "GND_G24") (pintype "power_in"))
      (node (ref "D2") (pin "G3") (pinfunction "GND_G3") (pintype "power_in"))
      (node (ref "D2") (pin "G4") (pinfunction "GND_G4") (pintype "power_in"))
      (node (ref "D2") (pin "H1") (pinfunction "GND_H1") (pintype "power_in"))
      (node (ref "D2") (pin "H11") (pinfunction "GND_H11") (pintype "power_in"))
      (node (ref "D2") (pin "H2") (pinfunction "GND_H2") (pintype "power_in"))
      (node (ref "D2") (pin "H5") (pinfunction "GND_H5") (pintype "power_in"))
      (node (ref "D2") (pin "J18") (pinfunction "GND_J18") (pintype "power_in"))
      (node (ref "D2") (pin "J22") (pinfunction "GND_J22") (pintype "power_in"))
      (node (ref "D2") (pin "J28") (pinfunction "GND_J28") (pintype "power_in"))
      (node (ref "D2") (pin "J3") (pinfunction "GND_J3") (pintype "power_in"))
      (node (ref "D2") (pin "J4") (pinfunction "GND_J4") (pintype "power_in"))
      (node (ref "D2") (pin "J6") (pinfunction "GND_J6") (pintype "power_in"))
      (node (ref "D2") (pin "J8") (pinfunction "GND_J8") (pintype "power_in"))
      (node (ref "D2") (pin "K1") (pinfunction "GND_K1") (pintype "power_in"))
      (node (ref "D2") (pin "K10") (pinfunction "GND_K10") (pintype "power_in"))
      (node (ref "D2") (pin "K15") (pinfunction "GND_K15") (pintype "power_in"))
      (node (ref "D2") (pin "K2") (pinfunction "GND_K2") (pintype "power_in"))
      (node (ref "D2") (pin "K20") (pinfunction "GND_K20") (pintype "power_in"))
      (node (ref "D2") (pin "K25") (pinfunction "GND_K25") (pintype "power_in"))
      (node (ref "D2") (pin "K5") (pinfunction "GND_K5") (pintype "power_in"))
      (node (ref "D2") (pin "L11") (pinfunction "GND_L11") (pintype "power_in"))
      (node (ref "D2") (pin "L13") (pinfunction "GND_L13") (pintype "power_in"))
      (node (ref "D2") (pin "L15") (pinfunction "GND_L15") (pintype "power_in"))
      (node (ref "D2") (pin "L17") (pinfunction "GND_L17") (pintype "power_in"))
      (node (ref "D2") (pin "L19") (pinfunction "GND_L19") (pintype "power_in"))
      (node (ref "D2") (pin "L22") (pinfunction "GND_L22") (pintype "power_in"))
      (node (ref "D2") (pin "L3") (pinfunction "GND_L3") (pintype "power_in"))
      (node (ref "D2") (pin "L4") (pinfunction "GND_L4") (pintype "power_in"))
      (node (ref "D2") (pin "L6") (pinfunction "GND_L6") (pintype "power_in"))
      (node (ref "D2") (pin "M1") (pinfunction "GND_M1") (pintype "power_in"))
      (node (ref "D2") (pin "M10") (pinfunction "GND_M10") (pintype "power_in"))
      (node (ref "D2") (pin "M12") (pinfunction "GND_M12") (pintype "power_in"))
      (node (ref "D2") (pin "M14") (pinfunction "GND_M14") (pintype "power_in"))
      (node (ref "D2") (pin "M16") (pinfunction "GND_M16") (pintype "power_in"))
      (node (ref "D2") (pin "M18") (pinfunction "GND_M18") (pintype "power_in"))
      (node (ref "D2") (pin "M2") (pinfunction "GND_M2") (pintype "power_in"))
      (node (ref "D2") (pin "M20") (pinfunction "GND_M20") (pintype "power_in"))
      (node (ref "D2") (pin "M29") (pinfunction "GND_M29") (pintype "power_in"))
      (node (ref "D2") (pin "M5") (pinfunction "GND_M5") (pintype "power_in"))
      (node (ref "D2") (pin "M7") (pinfunction "GND_M7") (pintype "power_in"))
      (node (ref "D2") (pin "M8") (pinfunction "GND_M8") (pintype "power_in"))
      (node (ref "D2") (pin "N11") (pinfunction "GND_N11") (pintype "power_in"))
      (node (ref "D2") (pin "N13") (pinfunction "GND_N13") (pintype "power_in"))
      (node (ref "D2") (pin "N15") (pinfunction "GND_N15") (pintype "power_in"))
      (node (ref "D2") (pin "N17") (pinfunction "GND_N17") (pintype "power_in"))
      (node (ref "D2") (pin "N19") (pinfunction "GND_N19") (pintype "power_in"))
      (node (ref "D2") (pin "N26") (pinfunction "GND_N26") (pintype "power_in"))
      (node (ref "D2") (pin "N3") (pinfunction "GND_N3") (pintype "power_in"))
      (node (ref "D2") (pin "N4") (pinfunction "GND_N4") (pintype "power_in"))
      (node (ref "D2") (pin "N6") (pinfunction "GND_N6") (pintype "power_in"))
      (node (ref "D2") (pin "N8") (pinfunction "GND_N8") (pintype "power_in"))
      (node (ref "D2") (pin "N9") (pinfunction "GND_N9") (pintype "power_in"))
      (node (ref "D2") (pin "P1") (pinfunction "GND_P1") (pintype "power_in"))
      (node (ref "D2") (pin "P10") (pinfunction "GND_P10") (pintype "power_in"))
      (node (ref "D2") (pin "P12") (pinfunction "GND_P12") (pintype "power_in"))
      (node (ref "D2") (pin "P14") (pinfunction "GND_P14") (pintype "power_in"))
      (node (ref "D2") (pin "P16") (pinfunction "GND_P16") (pintype "power_in"))
      (node (ref "D2") (pin "P18") (pinfunction "GND_P18") (pintype "power_in"))
      (node (ref "D2") (pin "P2") (pinfunction "GND_P2") (pintype "power_in"))
      (node (ref "D2") (pin "P20") (pinfunction "GND_P20") (pintype "power_in"))
      (node (ref "D2") (pin "P5") (pinfunction "GND_P5") (pintype "power_in"))
      (node (ref "D2") (pin "P7") (pinfunction "GND_P7") (pintype "power_in"))
      (node (ref "D2") (pin "R11") (pinfunction "GND_R11") (pintype "power_in"))
      (node (ref "D2") (pin "R13") (pinfunction "GND_R13") (pintype "power_in"))
      (node (ref "D2") (pin "R15") (pinfunction "GND_R15") (pintype "power_in"))
      (node (ref "D2") (pin "R17") (pinfunction "GND_R17") (pintype "power_in"))
      (node (ref "D2") (pin "R3") (pinfunction "GND_R3") (pintype "power_in"))
      (node (ref "D2") (pin "R30") (pinfunction "GND_R30") (pintype "power_in"))
      (node (ref "D2") (pin "R4") (pinfunction "GND_R4") (pintype "power_in"))
      (node (ref "D2") (pin "R6") (pinfunction "GND_R6") (pintype "power_in"))
      (node (ref "D2") (pin "R8") (pinfunction "GND_R8") (pintype "power_in"))
      (node (ref "D2") (pin "R9") (pinfunction "GND_R9") (pintype "power_in"))
      (node (ref "D2") (pin "T1") (pinfunction "GND_T1") (pintype "power_in"))
      (node (ref "D2") (pin "T10") (pinfunction "GND_T10") (pintype "power_in"))
      (node (ref "D2") (pin "T12") (pinfunction "GND_T12") (pintype "power_in"))
      (node (ref "D2") (pin "T14") (pinfunction "GND_T14") (pintype "power_in"))
      (node (ref "D2") (pin "T15") (pinfunction "GND_T15") (pintype "power_in"))
      (node (ref "D2") (pin "T16") (pinfunction "GND_T16") (pintype "power_in"))
      (node (ref "D2") (pin "T18") (pinfunction "GND_T18") (pintype "power_in"))
      (node (ref "D2") (pin "T2") (pinfunction "GND_T2") (pintype "power_in"))
      (node (ref "D2") (pin "T20") (pinfunction "GND_T20") (pintype "power_in"))
      (node (ref "D2") (pin "T27") (pinfunction "GND_T27") (pintype "power_in"))
      (node (ref "D2") (pin "T5") (pinfunction "GND_T5") (pintype "power_in"))
      (node (ref "D2") (pin "T7") (pinfunction "GND_T7") (pintype "power_in"))
      (node (ref "D2") (pin "U11") (pinfunction "GND_U11") (pintype "power_in"))
      (node (ref "D2") (pin "U13") (pinfunction "GND_U13") (pintype "power_in"))
      (node (ref "D2") (pin "U15") (pinfunction "GND_U15") (pintype "power_in"))
      (node (ref "D2") (pin "U17") (pinfunction "GND_U17") (pintype "power_in"))
      (node (ref "D2") (pin "U22") (pinfunction "GND_U22") (pintype "power_in"))
      (node (ref "D2") (pin "U24") (pinfunction "GND_U24") (pintype "power_in"))
      (node (ref "D2") (pin "U29") (pinfunction "GND_U29") (pintype "power_in"))
      (node (ref "D2") (pin "U3") (pinfunction "GND_U3") (pintype "power_in"))
      (node (ref "D2") (pin "U4") (pinfunction "GND_U4") (pintype "power_in"))
      (node (ref "D2") (pin "U6") (pinfunction "GND_U6") (pintype "power_in"))
      (node (ref "D2") (pin "U9") (pinfunction "GND_U9") (pintype "power_in"))
      (node (ref "D2") (pin "V1") (pinfunction "GND_V1") (pintype "power_in"))
      (node (ref "D2") (pin "V10") (pinfunction "GND_V10") (pintype "power_in"))
      (node (ref "D2") (pin "V12") (pinfunction "GND_V12") (pintype "power_in"))
      (node (ref "D2") (pin "V14") (pinfunction "GND_V14") (pintype "power_in"))
      (node (ref "D2") (pin "V19") (pinfunction "GND_V19") (pintype "power_in"))
      (node (ref "D2") (pin "V2") (pinfunction "GND_V2") (pintype "power_in"))
      (node (ref "D2") (pin "V21") (pinfunction "GND_V21") (pintype "power_in"))
      (node (ref "D2") (pin "V5") (pinfunction "GND_V5") (pintype "power_in"))
      (node (ref "D2") (pin "V7") (pinfunction "GND_V7") (pintype "power_in"))
      (node (ref "D2") (pin "W11") (pinfunction "GND_W11") (pintype "power_in"))
      (node (ref "D2") (pin "W13") (pinfunction "GND_W13") (pintype "power_in"))
      (node (ref "D2") (pin "W18") (pinfunction "GND_W18") (pintype "power_in"))
      (node (ref "D2") (pin "W28") (pinfunction "GND_W28") (pintype "power_in"))
      (node (ref "D2") (pin "W3") (pinfunction "GND_W3") (pintype "power_in"))
      (node (ref "D2") (pin "W4") (pinfunction "GND_W4") (pintype "power_in"))
      (node (ref "D2") (pin "W6") (pinfunction "GND_W6") (pintype "power_in"))
      (node (ref "D2") (pin "W9") (pinfunction "GND_W9") (pintype "power_in"))
      (node (ref "D2") (pin "Y1") (pinfunction "GND_Y1") (pintype "power_in"))
      (node (ref "D2") (pin "Y10") (pinfunction "GND_Y10") (pintype "power_in"))
      (node (ref "D2") (pin "Y12") (pinfunction "GND_Y12") (pintype "power_in"))
      (node (ref "D2") (pin "Y14") (pinfunction "GND_Y14") (pintype "power_in"))
      (node (ref "D2") (pin "Y15") (pinfunction "GND_Y15") (pintype "power_in"))
      (node (ref "D2") (pin "Y2") (pinfunction "GND_Y2") (pintype "power_in"))
      (node (ref "D2") (pin "Y20") (pinfunction "GND_Y20") (pintype "power_in"))
      (node (ref "D2") (pin "Y25") (pinfunction "GND_Y25") (pintype "power_in"))
      (node (ref "D2") (pin "Y30") (pinfunction "GND_Y30") (pintype "power_in"))
      (node (ref "D2") (pin "Y5") (pinfunction "GND_Y5") (pintype "power_in"))
      (node (ref "D2") (pin "Y7") (pinfunction "GND_Y7") (pintype "power_in"))
      (node (ref "D2") (pin "Y8") (pinfunction "GND_Y8") (pintype "power_in"))
    )
    (net (code "4") (name "VCC1P1") (class "Default")
      (node (ref "C113") (pin "2") (pinfunction "-_2") (pintype "passive"))
      (node (ref "C114") (pin "2") (pinfunction "-_2") (pintype "passive"))
      (node (ref "C115") (pin "2") (pinfunction "-_2") (pintype "passive"))
      (node (ref "C116") (pin "2") (pinfunction "-_2") (pintype "passive"))
      (node (ref "C117") (pin "2") (pinfunction "-_2") (pintype "passive"))
      (node (ref "C118") (pin "2") (pinfunction "-_2") (pintype "passive"))
      (node (ref "C119") (pin "2") (pinfunction "-_2") (pintype "passive"))
      (node (ref "C120") (pin "2") (pinfunction "-_2") (pintype "passive"))
      (node (ref "C127") (pin "2") (pinfunction "-_2") (pintype "passive"))
      (node (ref "C128") (pin "2") (pinfunction "-_2") (pintype "passive"))
      (node (ref "C129") (pin "2") (pinfunction "-_2") (pintype "passive"))
      (node (ref "C130") (pin "2") (pinfunction "-_2") (pintype "passive"))
      (node (ref "C131") (pin "2") (pinfunction "-_2") (pintype "passive"))
      (node (ref "C132") (pin "2") (pinfunction "-_2") (pintype "passive"))
      (node (ref "C133") (pin "2") (pinfunction "-_2") (pintype "passive"))
      (node (ref "C134") (pin "2") (pinfunction "-_2") (pintype "passive"))
      (node (ref "C146") (pin "2") (pinfunction "-_2") (pintype "passive"))
      (node (ref "C147") (pin "2") (pinfunction "-_2") (pintype "passive"))
      (node (ref "C148") (pin "2") (pinfunction "-_2") (pintype "passive"))
      (node (ref "C149") (pin "2") (pinfunction "-_2") (pintype "passive"))
      (node (ref "C150") (pin "2") (pinfunction "-_2") (pintype "passive"))
      (node (ref "C151") (pin "2") (pinfunction "-_2") (pintype "passive"))
      (node (ref "C152") (pin "2") (pinfunction "-_2") (pintype "passive"))
      (node (ref "C153") (pin "2") (pinfunction "-_2") (pintype "passive"))
      (node (ref "C168") (pin "1") (pinfunction "+_1") (pintype "passive"))
      (node (ref "C169") (pin "1") (pinfunction "+_1") (pintype "passive"))
      (node (ref "C170") (pin "1") (pinfunction "+_1") (pintype "passive"))
      (node (ref "C171") (pin "1") (pinfunction "+_1") (pintype "passive"))
      (node (ref "C172") (pin "1") (pinfunction "+_1") (pintype "passive"))
      (node (ref "C173") (pin "1") (pinfunction "+_1") (pintype "passive"))
      (node (ref "C174") (pin "1") (pinfunction "+_1") (pintype "passive"))
      (node (ref "C180") (pin "1") (pinfunction "+_1") (pintype "passive"))
      (node (ref "C181") (pin "1") (pinfunction "+_1") (pintype "passive"))
      (node (ref "C182") (pin "1") (pinfunction "+_1") (pintype "passive"))
      (node (ref "C183") (pin "1") (pinfunction "+_1") (pintype "passive"))
      (node (ref "C184") (pin "1") (pinfunction "+_1") (pintype "passive"))
      (node (ref "C185") (pin "1") (pinfunction "+_1") (pintype "passive"))
      (node (ref "C186") (pin "1") (pinfunction "+_1") (pintype "passive"))
      (node (ref "C187") (pin "1") (pinfunction "+_1") (pintype "passive"))
      (node (ref "C189") (pin "1") (pinfunction "+_1") (pintype "passive"))
      (node (ref "C190") (pin "1") (pinfunction "+_1") (pintype "passive"))
      (node (ref "C191") (pin "1") (pinfunction "+_1") (pintype "passive"))
      (node (ref "C192") (pin "1") (pinfunction "+_1") (pintype "passive"))
      (node (ref "C193") (pin "1") (pinfunction "+_1") (pintype "passive"))
      (node (ref "C199") (pin "2") (pinfunction "-_2") (pintype "passive"))
      (node (ref "C200") (pin "2") (pinfunction "-_2") (pintype "passive"))
      (node (ref "C201") (pin "2") (pinfunction "-_2") (pintype "passive"))
      (node (ref "C202") (pin "1") (pinfunction "+_1") (pintype "passive"))
      (node (ref "C203") (pin "1") (pinfunction "+_1") (pintype "passive"))
      (node (ref "C204") (pin "1") (pinfunction "+_1") (pintype "passive"))
      (node (ref "C205") (pin "1") (pinfunction "+_1") (pintype "passive"))
      (node (ref "C210") (pin "2") (pinfunction "-_2") (pintype "passive"))
      (node (ref "C211") (pin "2") (pinfunction "-_2") (pintype "passive"))
      (node (ref "C212") (pin "2") (pinfunction "-_2") (pintype "passive"))
      (node (ref "C213") (pin "2") (pinfunction "-_2") (pintype "passive"))
      (node (ref "C214") (pin "2") (pinfunction "-_2") (pintype "passive"))
      (node (ref "C215") (pin "2") (pinfunction "-_2") (pintype "passive"))
      (node (ref "C216") (pin "2") (pinfunction "-_2") (pintype "passive"))
      (node (ref "C94") (pin "1") (pinfunction "+_1") (pintype "passive"))
      (node (ref "D2") (pin "L16") (pinfunction "VCC_HPS_L16") (pintype "power_in"))
      (node (ref "D2") (pin "L18") (pinfunction "VCC_HPS_L18") (pintype "power_in"))
      (node (ref "D2") (pin "L20") (pinfunction "VCC_HPS_L20") (pintype "power_in"))
      (node (ref "D2") (pin "M11") (pinfunction "VCC_M11") (pintype "power_in"))
      (node (ref "D2") (pin "M13") (pinfunction "VCC_M13") (pintype "power_in"))
      (node (ref "D2") (pin "M15") (pinfunction "VCC_HPS_M15") (pintype "power_in"))
      (node (ref "D2") (pin "M9") (pinfunction "VCC_M9") (pintype "power_in"))
      (node (ref "D2") (pin "N10") (pinfunction "VCC_N10") (pintype "power_in"))
      (node (ref "D2") (pin "N12") (pinfunction "VCC_N12") (pintype "power_in"))
      (node (ref "D2") (pin "N14") (pinfunction "VCC_N14") (pintype "power_in"))
      (node (ref "D2") (pin "N20") (pinfunction "VCC_HPS_N20") (pintype "power_in"))
      (node (ref "D2") (pin "P11") (pinfunction "VCC_P11") (pintype "power_in"))
      (node (ref "D2") (pin "P13") (pinfunction "VCC_P13") (pintype "power_in"))
      (node (ref "D2") (pin "P15") (pinfunction "VCC_HPS_P15") (pintype "power_in"))
      (node (ref "D2") (pin "P17") (pinfunction "VCC_HPS_P17") (pintype "power_in"))
      (node (ref "D2") (pin "P19") (pinfunction "VCC_HPS_P19") (pintype "power_in"))
      (node (ref "D2") (pin "R10") (pinfunction "VCC_R10") (pintype "power_in"))
      (node (ref "D2") (pin "R12") (pinfunction "VCC_R12") (pintype "power_in"))
      (node (ref "D2") (pin "R14") (pinfunction "VCC_R14") (pintype "power_in"))
      (node (ref "D2") (pin "R16") (pinfunction "VCC_HPS_R16") (pintype "power_in"))
      (node (ref "D2") (pin "T11") (pinfunction "VCC_T11") (pintype "power_in"))
      (node (ref "D2") (pin "T13") (pinfunction "VCC_T13") (pintype "power_in"))
      (node (ref "D2") (pin "T17") (pinfunction "VCC_HPS_T17") (pintype "power_in"))
      (node (ref "D2") (pin "T19") (pinfunction "VCC_HPS_T19") (pintype "power_in"))
      (node (ref "D2") (pin "U10") (pinfunction "VCC_U10") (pintype "power_in"))
      (node (ref "D2") (pin "U12") (pinfunction "VCC_U12") (pintype "power_in"))
      (node (ref "D2") (pin "U14") (pinfunction "VCC_U14") (pintype "power_in"))
      (node (ref "D2") (pin "U16") (pinfunction "VCC_HPS_U16") (pintype "power_in"))
      (node (ref "D2") (pin "U18") (pinfunction "VCC_HPS_U18") (pintype "power_in"))
      (node (ref "D2") (pin "U21") (pinfunction "VCC_U21") (pintype "power_in"))
      (node (ref "D2") (pin "V11") (pinfunction "VCC_V11") (pintype "power_in"))
      (node (ref "D2") (pin "V13") (pinfunction "VCC_V13") (pintype "power_in"))
      (node (ref "D2") (pin "V15") (pinfunction "VCC_V15") (pintype "power_in"))
      (node (ref "D2") (pin "W10") (pinfunction "VCC_W10") (pintype "power_in"))
      (node (ref "D2") (pin "W12") (pinfunction "VCC_W12") (pintype "power_in"))
      (node (ref "D2") (pin "W14") (pinfunction "VCC_W14") (pintype "power_in"))
      (node (ref "D2") (pin "Y11") (pinfunction "VCC_Y11") (pintype "power_in"))
      (node (ref "D2") (pin "Y13") (pinfunction "VCC_Y13") (pintype "power_in"))
      (node (ref "D2") (pin "Y9") (pinfunction "VCC_Y9") (pintype "power_in"))
      (node (ref "L2") (pin "2") (pinfunction "2_2") (pintype "passive"))
    )
    (net (code "5") (name "VCC1P5_DDR3") (class "Default")
      (node (ref "C107") (pin "2") (pinfunction "-_2") (pintype "passive"))
      (node (ref "C108") (pin "2") (pinfunction "-_2") (pintype "passive"))
      (node (ref "C109") (pin "2") (pinfunction "-_2") (pintype "passive"))
      (node (ref "C110") (pin "2") (pinfunction "-_2") (pintype "passive"))
      (node (ref "C111") (pin "2") (pinfunction "-_2") (pintype "passive"))
      (node (ref "C175") (pin "1") (pinfunction "+_1") (pintype "passive"))
      (node (ref "C194") (pin "2") (pinfunction "-_2") (pintype "passive"))
      (node (ref "C195") (pin "2") (pinfunction "-_2") (pintype "passive"))
      (node (ref "C196") (pin "2") (pinfunction "-_2") (pintype "passive"))
      (node (ref "C197") (pin "2") (pinfunction "-_2") (pintype "passive"))
      (node (ref "C198") (pin "2") (pinfunction "-_2") (pintype "passive"))
      (node (ref "C220") (pin "2") (pinfunction "-_2") (pintype "passive"))
      (node (ref "C221") (pin "2") (pinfunction "-_2") (pintype "passive"))
      (node (ref "C222") (pin "2") (pinfunction "-_2") (pintype "passive"))
      (node (ref "C223") (pin "2") (pinfunction "-_2") (pintype "passive"))
      (node (ref "C224") (pin "2") (pinfunction "-_2") (pintype "passive"))
      (node (ref "C225") (pin "2") (pinfunction "-_2") (pintype "passive"))
      (node (ref "C227") (pin "1") (pinfunction "+_1") (pintype "passive"))
      (node (ref "C228") (pin "1") (pinfunction "+_1") (pintype "passive"))
      (node (ref "C229") (pin "2") (pinfunction "-_2") (pintype "passive"))
      (node (ref "C230") (pin "2") (pinfunction "-_2") (pintype "passive"))
      (node (ref "C231") (pin "2") (pinfunction "-_2") (pintype "passive"))
      (node (ref "C236") (pin "2") (pinfunction "-_2") (pintype "passive"))
      (node (ref "C237") (pin "2") (pinfunction "-_2") (pintype "passive"))
      (node (ref "C238") (pin "2") (pinfunction "-_2") (pintype "passive"))
      (node (ref "C239") (pin "2") (pinfunction "-_2") (pintype "passive"))
      (node (ref "C240") (pin "2") (pinfunction "-_2") (pintype "passive"))
      (node (ref "C241") (pin "2") (pinfunction "-_2") (pintype "passive"))
      (node (ref "C246") (pin "1") (pinfunction "+_1") (pintype "passive"))
      (node (ref "C247") (pin "1") (pinfunction "+_1") (pintype "passive"))
      (node (ref "C248") (pin "2") (pinfunction "-_2") (pintype "passive"))
      (node (ref "C249") (pin "2") (pinfunction "-_2") (pintype "passive"))
      (node (ref "C250") (pin "2") (pinfunction "-_2") (pintype "passive"))
      (node (ref "C271") (pin "2") (pinfunction "-_2") (pintype "passive"))
      (node (ref "C272") (pin "2") (pinfunction "-_2") (pintype "passive"))
      (node (ref "C273") (pin "1") (pinfunction "+_1") (pintype "passive"))
      (node (ref "C274") (pin "1") (pinfunction "+_1") (pintype "passive"))
      (node (ref "C275") (pin "1") (pinfunction "+_1") (pintype "passive"))
      (node (ref "C276") (pin "1") (pinfunction "+_1") (pintype "passive"))
      (node (ref "C277") (pin "1") (pinfunction "+_1") (pintype "passive"))
      (node (ref "C278") (pin "1") (pinfunction "+_1") (pintype "passive"))
      (node (ref "C279") (pin "1") (pinfunction "+_1") (pintype "passive"))
      (node (ref "C280") (pin "1") (pinfunction "+_1") (pintype "passive"))
      (node (ref "C281") (pin "1") (pinfunction "+_1") (pintype "passive"))
      (node (ref "C282") (pin "1") (pinfunction "+_1") (pintype "passive"))
      (node (ref "D2") (pin "AA17") (pinfunction "VCCIO4A_AA17") (pintype "power_in"))
      (node (ref "D2") (pin "AB14") (pinfunction "VCCIO3B_AB14") (pintype "power_in"))
      (node (ref "D2") (pin "AC21") (pinfunction "VCCIO4A_AC21") (pintype "power_in"))
      (node (ref "D2") (pin "AD13") (pinfunction "VCCIO3B_AD13") (pintype "power_in"))
      (node (ref "D2") (pin "AD18") (pinfunction "VCCIO4A_AD18") (pintype "power_in"))
      (node (ref "D2") (pin "AE15") (pinfunction "VCCIO3B_AE15") (pintype "power_in"))
      (node (ref "D2") (pin "AE25") (pinfunction "VCCIO4A_AE25") (pintype "power_in"))
      (node (ref "D2") (pin "AF22") (pinfunction "VCCIO4A_AF22") (pintype "power_in"))
      (node (ref "D2") (pin "AG19") (pinfunction "VCCIO4A_AG19") (pintype "power_in"))
      (node (ref "D2") (pin "AH16") (pinfunction "VCCIO4A_AH16") (pintype "power_in"))
      (node (ref "D2") (pin "AH26") (pinfunction "VCCIO4A_AH26") (pintype "power_in"))
      (node (ref "D2") (pin "AJ13") (pinfunction "VCCIO3B_AJ13") (pintype "power_in"))
      (node (ref "D2") (pin "AJ23") (pinfunction "VCCIO4A_AJ23") (pintype "power_in"))
      (node (ref "D2") (pin "AJ8") (pinfunction "VCCIO3B_AJ8") (pintype "power_in"))
      (node (ref "D2") (pin "AK10") (pinfunction "VCCIO3B_AK10") (pintype "power_in"))
      (node (ref "D2") (pin "AK20") (pinfunction "VCCIO4A_AK20") (pintype "power_in"))
      (node (ref "D2") (pin "D28") (pinfunction "VCCIO6A_HPS_D28") (pintype "power_in"))
      (node (ref "D2") (pin "G29") (pinfunction "VCCIO6A_HPS_G29") (pintype "power_in"))
      (node (ref "D2") (pin "H26") (pinfunction "VCCIO6A_HPS_H26") (pintype "power_in"))
      (node (ref "D2") (pin "K24") (pinfunction "VCCIO6A_HPS_K24") (pintype "power_in"))
      (node (ref "D2") (pin "K30") (pinfunction "VCCIO6A_HPS_K30") (pintype "power_in"))
      (node (ref "D2") (pin "L27") (pinfunction "VCCIO6A_HPS_L27") (pintype "power_in"))
      (node (ref "D2") (pin "M24") (pinfunction "VCCIO6A_HPS_M24") (pintype "power_in"))
      (node (ref "D2") (pin "N21") (pinfunction "VCCIO6A_HPS_N21") (pintype "power_in"))
      (node (ref "D2") (pin "P23") (pinfunction "VCCIO6B_HPS_P23") (pintype "power_in"))
      (node (ref "D2") (pin "P28") (pinfunction "VCCIO6B_HPS_P28") (pintype "power_in"))
      (node (ref "D2") (pin "R25") (pinfunction "VCCIO6B_HPS_R25") (pintype "power_in"))
      (node (ref "D2") (pin "T22") (pinfunction "VCCIO6B_HPS_T22") (pintype "power_in"))
      (node (ref "D2") (pin "U19") (pinfunction "VCCIO6B_HPS_U19") (pintype "power_in"))
      (node (ref "D2") (pin "V26") (pinfunction "VCCIO6B_HPS_V26") (pintype "power_in"))
    )
    (net (code "6") (name "VCC2P5") (class "Default")
      (node (ref "C112") (pin "1") (pinfunction "+_1") (pintype "passive"))
      (node (ref "C121") (pin "2") (pinfunction "-_2") (pintype "passive"))
      (node (ref "C122") (pin "2") (pinfunction "-_2") (pintype "passive"))
      (node (ref "C135") (pin "2") (pinfunction "-_2") (pintype "passive"))
      (node (ref "C136") (pin "2") (pinfunction "-_2") (pintype "passive"))
      (node (ref "C137") (pin "1") (pinfunction "+_1") (pintype "passive"))
      (node (ref "C142") (pin "2") (pinfunction "-_2") (pintype "passive"))
      (node (ref "C143") (pin "2") (pinfunction "-_2") (pintype "passive"))
      (node (ref "C144") (pin "2") (pinfunction "-_2") (pintype "passive"))
      (node (ref "C145") (pin "2") (pinfunction "-_2") (pintype "passive"))
      (node (ref "C154") (pin "1") (pinfunction "+_1") (pintype "passive"))
      (node (ref "C164") (pin "2") (pinfunction "-_2") (pintype "passive"))
      (node (ref "C165") (pin "2") (pinfunction "-_2") (pintype "passive"))
      (node (ref "C166") (pin "2") (pinfunction "-_2") (pintype "passive"))
      (node (ref "C206") (pin "2") (pinfunction "-_2") (pintype "passive"))
      (node (ref "C207") (pin "2") (pinfunction "-_2") (pintype "passive"))
      (node (ref "C259") (pin "2") (pinfunction "-_2") (pintype "passive"))
      (node (ref "C260") (pin "2") (pinfunction "-_2") (pintype "passive"))
      (node (ref "C261") (pin "2") (pinfunction "-_2") (pintype "passive"))
      (node (ref "C262") (pin "2") (pinfunction "-_2") (pintype "passive"))
      (node (ref "C263") (pin "2") (pinfunction "-_2") (pintype "passive"))
      (node (ref "C264") (pin "2") (pinfunction "-_2") (pintype "passive"))
      (node (ref "C265") (pin "2") (pinfunction "-_2") (pintype "passive"))
      (node (ref "C266") (pin "2") (pinfunction "-_2") (pintype "passive"))
      (node (ref "C87") (pin "1") (pinfunction "+_1") (pintype "passive"))
      (node (ref "D2") (pin "A7") (pinfunction "VCCIO8A_A7") (pintype "power_in"))
      (node (ref "D2") (pin "AA10") (pinfunction "VCCPD3A_AA10") (pintype "power_in"))
      (node (ref "D2") (pin "AA27") (pinfunction "VCCIO5B_AA27") (pintype "power_in"))
      (node (ref "D2") (pin "AB18") (pinfunction "VCCPD3B4A_AB18") (pintype "power_in"))
      (node (ref "D2") (pin "AB20") (pinfunction "VCCPD3B4A_AB20") (pintype "power_in"))
      (node (ref "D2") (pin "AB24") (pinfunction "VCCIO5A_AB24") (pintype "power_in"))
      (node (ref "D2") (pin "AC10") (pinfunction "VCCPD3A_AC10") (pintype "power_in"))
      (node (ref "D2") (pin "AC11") (pinfunction "VCCIO3A_AC11") (pintype "power_in"))
      (node (ref "D2") (pin "AC13") (pinfunction "VCCPD3B4A_AC13") (pintype "power_in"))
      (node (ref "D2") (pin "AC15") (pinfunction "VCCPD3B4A_AC15") (pintype "power_in"))
      (node (ref "D2") (pin "AC17") (pinfunction "VCCPD3B4A_AC17") (pintype "power_in"))
      (node (ref "D2") (pin "AC19") (pinfunction "VCCPD3B4A_AC19") (pintype "power_in"))
      (node (ref "D2") (pin "AD16") (pinfunction "VCCPD3B4A_AD16") (pintype "power_in"))
      (node (ref "D2") (pin "AD28") (pinfunction "VCCIO5A_AD28") (pintype "power_in"))
      (node (ref "D2") (pin "AD8") (pinfunction "VCCIO3A_AD8") (pintype "power_in"))
      (node (ref "D2") (pin "AE21") (pinfunction "VCCPD3B4A_AE21") (pintype "power_in"))
      (node (ref "D2") (pin "AE30") (pinfunction "VCCIO5B_AE30") (pintype "power_in"))
      (node (ref "D2") (pin "AF7") (pinfunction "VCCIO3A_AF7") (pintype "power_in"))
      (node (ref "D2") (pin "AG29") (pinfunction "VCCIO5A_AG29") (pintype "power_in"))
      (node (ref "D2") (pin "AG4") (pinfunction "VCCIO3A_AG4") (pintype "power_in"))
      (node (ref "D2") (pin "B4") (pinfunction "VCCIO8A_B4") (pintype "power_in"))
      (node (ref "D2") (pin "C11") (pinfunction "VCCIO8A_C11") (pintype "power_in"))
      (node (ref "D2") (pin "D8") (pinfunction "VCCIO8A_D8") (pintype "power_in"))
      (node (ref "D2") (pin "E5") (pinfunction "VCCIO8A_E5") (pintype "power_in"))
      (node (ref "D2") (pin "F12") (pinfunction "VCCIO8A_F12") (pintype "power_in"))
      (node (ref "D2") (pin "G14") (pinfunction "VCCIO8A_G14") (pintype "power_in"))
      (node (ref "D2") (pin "G9") (pinfunction "VCCIO8A_G9") (pintype "power_in"))
      (node (ref "D2") (pin "H6") (pinfunction "VCCIO8A_H6") (pintype "power_in"))
      (node (ref "D2") (pin "J13") (pinfunction "VCCIO8A_J13") (pintype "power_in"))
      (node (ref "D2") (pin "K11") (pinfunction "VCCPD8A_K11") (pintype "power_in"))
      (node (ref "D2") (pin "K13") (pinfunction "VCCPD8A_K13") (pintype "power_in"))
      (node (ref "D2") (pin "L10") (pinfunction "VCCPD8A_L10") (pintype "power_in"))
      (node (ref "D2") (pin "L12") (pinfunction "VCCPD8A_L12") (pintype "power_in"))
      (node (ref "D2") (pin "L14") (pinfunction "VCCPD8A_L14") (pintype "power_in"))
      (node (ref "D2") (pin "M21") (pinfunction "VCCPD6A6B_HPS_M21") (pintype "power_in"))
      (node (ref "D2") (pin "N22") (pinfunction "VCCPD6A6B_HPS_N22") (pintype "power_in"))
      (node (ref "D2") (pin "P21") (pinfunction "VCCPD6A6B_HPS_P21") (pintype "power_in"))
      (node (ref "D2") (pin "R20") (pinfunction "VCCPD6A6B_HPS_R20") (pintype "power_in"))
      (node (ref "D2") (pin "R23") (pinfunction "VCCPD6A6B_HPS_R23") (pintype "power_in"))
      (node (ref "D2") (pin "U23") (pinfunction "VCCPD5B_U23") (pintype "power_in"))
      (node (ref "D2") (pin "V22") (pinfunction "VCCPD5A_V22") (pintype "power_in"))
      (node (ref "D2") (pin "V24") (pinfunction "VCCPD5A_V24") (pintype "power_in"))
      (node (ref "D2") (pin "W23") (pinfunction "VCCIO5A_W23") (pintype "power_in"))
      (node (ref "L1") (pin "2") (pinfunction "2_2") (pintype "passive"))
      (node (ref "L13") (pin "2") (pinfunction "2_2") (pintype "passive"))
      (node (ref "L3") (pin "2") (pinfunction "2_2") (pintype "passive"))
      (node (ref "L4") (pin "2") (pinfunction "2_2") (pintype "passive"))
      (node (ref "L5") (pin "1") (pinfunction "1_1") (pintype "passive"))
    )
    (net (code "7") (name "VCC3P3") (class "Default")
      (node (ref "C208") (pin "2") (pinfunction "-_2") (pintype "passive"))
      (node (ref "C209") (pin "2") (pinfunction "-_2") (pintype "passive"))
      (node (ref "C217") (pin "2") (pinfunction "-_2") (pintype "passive"))
      (node (ref "C218") (pin "2") (pinfunction "-_2") (pintype "passive"))
      (node (ref "C219") (pin "2") (pinfunction "-_2") (pintype "passive"))
      (node (ref "C226") (pin "2") (pinfunction "-_2") (pintype "passive"))
      (node (ref "C251") (pin "2") (pinfunction "-_2") (pintype "passive"))
      (node (ref "C252") (pin "2") (pinfunction "-_2") (pintype "passive"))
      (node (ref "C253") (pin "2") (pinfunction "-_2") (pintype "passive"))
      (node (ref "C254") (pin "2") (pinfunction "-_2") (pintype "passive"))
      (node (ref "C255") (pin "2") (pinfunction "-_2") (pintype "passive"))
      (node (ref "C256") (pin "2") (pinfunction "-_2") (pintype "passive"))
      (node (ref "C257") (pin "2") (pinfunction "-_2") (pintype "passive"))
      (node (ref "C258") (pin "2") (pinfunction "-_2") (pintype "passive"))
      (node (ref "D2") (pin "AA23") (pinfunction "VCCPGM_AA23") (pintype "power_in"))
      (node (ref "D2") (pin "AB10") (pinfunction "VCCPGM_AB10") (pintype "power_in"))
      (node (ref "D2") (pin "D18") (pinfunction "VCCIO7C_HPS_D18") (pintype "power_in"))
      (node (ref "D2") (pin "E15") (pinfunction "VCCIO7D_HPS_E15") (pintype "power_in"))
      (node (ref "D2") (pin "E20") (pinfunction "VCCIO7B_HPS_E20") (pintype "power_in"))
      (node (ref "D2") (pin "F22") (pinfunction "VCCIO7A_HPS_F22") (pintype "power_in"))
      (node (ref "D2") (pin "G19") (pinfunction "VCCIO7B_HPS_G19") (pintype "power_in"))
      (node (ref "D2") (pin "H16") (pinfunction "VCCIO7D_HPS_H16") (pintype "power_in"))
      (node (ref "D2") (pin "H21") (pinfunction "VCCIO7A_HPS_H21") (pintype "power_in"))
      (node (ref "D2") (pin "J11") (pinfunction "VCCPGM_J11") (pintype "power_in"))
      (node (ref "D2") (pin "J17") (pinfunction "VCCPD7C_HPS_J17") (pintype "power_in"))
      (node (ref "D2") (pin "K16") (pinfunction "VCCPD7D_HPS_K16") (pintype "power_in"))
      (node (ref "D2") (pin "K18") (pinfunction "VCCPD7B_HPS_K18") (pintype "power_in"))
      (node (ref "D2") (pin "K19") (pinfunction "VCCPD7A_HPS_K19") (pintype "power_in"))
      (node (ref "L6") (pin "1") (pinfunction "1_1") (pintype "passive"))
    )
    (net (code "8") (name "VCCAUX_2p5") (class "Default")
      (node (ref "C138") (pin "2") (pinfunction "-_2") (pintype "passive"))
      (node (ref "C139") (pin "2") (pinfunction "-_2") (pintype "passive"))
      (node (ref "C140") (pin "2") (pinfunction "-_2") (pintype "passive"))
      (node (ref "C141") (pin "2") (pinfunction "-_2") (pintype "passive"))
      (node (ref "D2") (pin "AB11") (pinfunction "VCC_AUX_AB11") (pintype "power_in"))
      (node (ref "D2") (pin "AB16") (pinfunction "VCC_AUX_AB16") (pintype "power_in"))
      (node (ref "D2") (pin "AD22") (pinfunction "VCC_AUX_AD22") (pintype "power_in"))
      (node (ref "D2") (pin "H10") (pinfunction "VCC_AUX_H10") (pintype "power_in"))
      (node (ref "D2") (pin "J16") (pinfunction "VCC_AUX_J16") (pintype "power_in"))
      (node (ref "L3") (pin "1") (pinfunction "1_1") (pintype "passive"))
    )
    (net (code "9") (name "VCCAUX_SH_2p5") (class "Default")
      (node (ref "C176") (pin "2") (pinfunction "-_2") (pintype "passive"))
      (node (ref "C177") (pin "2") (pinfunction "-_2") (pintype "passive"))
      (node (ref "C178") (pin "2") (pinfunction "-_2") (pintype "passive"))
      (node (ref "C179") (pin "2") (pinfunction "-_2") (pintype "passive"))
      (node (ref "D2") (pin "J21") (pinfunction "VCC_AUX_SHARED_J21") (pintype "power_in"))
      (node (ref "L4") (pin "1") (pinfunction "1_1") (pintype "passive"))
    )
    (net (code "10") (name "VCCA_FPLL_2p5") (class "Default")
      (node (ref "C155") (pin "2") (pinfunction "-_2") (pintype "passive"))
      (node (ref "C156") (pin "2") (pinfunction "-_2") (pintype "passive"))
      (node (ref "C157") (pin "2") (pinfunction "-_2") (pintype "passive"))
      (node (ref "C158") (pin "2") (pinfunction "-_2") (pintype "passive"))
      (node (ref "C159") (pin "2") (pinfunction "-_2") (pintype "passive"))
      (node (ref "C160") (pin "2") (pinfunction "-_2") (pintype "passive"))
      (node (ref "C161") (pin "2") (pinfunction "-_2") (pintype "passive"))
      (node (ref "C162") (pin "1") (pinfunction "+_1") (pintype "passive"))
      (node (ref "C163") (pin "1") (pinfunction "+_1") (pintype "passive"))
      (node (ref "D2") (pin "AA8") (pinfunction "VCCA_FPLL_AA8") (pintype "power_in"))
      (node (ref "D2") (pin "K9") (pinfunction "VCCA_FPLL_K9") (pintype "power_in"))
      (node (ref "D2") (pin "N7") (pinfunction "VCCA_FPLL_N7") (pintype "power_in"))
      (node (ref "D2") (pin "R7") (pinfunction "VCCA_FPLL_R7") (pintype "power_in"))
      (node (ref "D2") (pin "V8") (pinfunction "VCCA_FPLL_V8") (pintype "power_in"))
      (node (ref "D2") (pin "Y22") (pinfunction "VCCA_FPLL_Y22") (pintype "power_in"))
      (node (ref "L13") (pin "1") (pinfunction "1_1") (pintype "passive"))
    )
    (net (code "11") (name "VCCH_GXBL_2p5") (class "Default")
      (node (ref "C123") (pin "2") (pinfunction "-_2") (pintype "passive"))
      (node (ref "C124") (pin "2") (pinfunction "-_2") (pintype "passive"))
      (node (ref "C125") (pin "2") (pinfunction "-_2") (pintype "passive"))
      (node (ref "C126") (pin "2") (pinfunction "-_2") (pintype "passive"))
      (node (ref "D2") (pin "AB6") (pinfunction "VCCH_GXBL_AB6") (pintype "power_in"))
      (node (ref "D2") (pin "P6") (pinfunction "VCCH_GXBL_P6") (pintype "power_in"))
      (node (ref "D2") (pin "V6") (pinfunction "VCCH_GXBL_V6") (pintype "power_in"))
      (node (ref "L1") (pin "1") (pinfunction "1_1") (pintype "passive"))
    )
    (net (code "12") (name "VCCL_GXBL_1p1") (class "Default")
      (node (ref "C103") (pin "2") (pinfunction "-_2") (pintype "passive"))
      (node (ref "C105") (pin "2") (pinfunction "-_2") (pintype "passive"))
      (node (ref "C106") (pin "2") (pinfunction "-_2") (pintype "passive"))
      (node (ref "C70") (pin "2") (pinfunction "-_2") (pintype "passive"))
      (node (ref "D2") (pin "AA5") (pinfunction "VCCE_GXBL_AA5") (pintype "power_in"))
      (node (ref "D2") (pin "L5") (pinfunction "VCCL_GXBL_L5") (pintype "power_in"))
      (node (ref "D2") (pin "M6") (pinfunction "VCCE_GXBL_M6") (pintype "power_in"))
      (node (ref "D2") (pin "N5") (pinfunction "VCCE_GXBL_N5") (pintype "power_in"))
      (node (ref "D2") (pin "R5") (pinfunction "VCCL_GXBL_R5") (pintype "power_in"))
      (node (ref "D2") (pin "T6") (pinfunction "VCCE_GXBL_T6") (pintype "power_in"))
      (node (ref "D2") (pin "U5") (pinfunction "VCCE_GXBL_U5") (pintype "power_in"))
      (node (ref "D2") (pin "W5") (pinfunction "VCCL_GXBL_W5") (pintype "power_in"))
      (node (ref "D2") (pin "Y6") (pinfunction "VCCE_GXBL_Y6") (pintype "power_in"))
      (node (ref "L2") (pin "1") (pinfunction "1_1") (pintype "passive"))
    )
    (net (code "13") (name "VCCPLL_HPS_2p5") (class "Default")
      (node (ref "C232") (pin "2") (pinfunction "-_2") (pintype "passive"))
      (node (ref "C233") (pin "2") (pinfunction "-_2") (pintype "passive"))
      (node (ref "C234") (pin "2") (pinfunction "-_2") (pintype "passive"))
      (node (ref "C235") (pin "2") (pinfunction "-_2") (pintype "passive"))
      (node (ref "D2") (pin "L21") (pinfunction "VCCPLL_HPS_L21") (pintype "power_in"))
      (node (ref "L5") (pin "2") (pinfunction "2_2") (pintype "passive"))
    )
    (net (code "14") (name "VCCRSTCLK_HPS") (class "Default")
      (node (ref "C242") (pin "2") (pinfunction "-_2") (pintype "passive"))
      (node (ref "C243") (pin "2") (pinfunction "-_2") (pintype "passive"))
      (node (ref "C244") (pin "2") (pinfunction "-_2") (pintype "passive"))
      (node (ref "C245") (pin "2") (pinfunction "-_2") (pintype "passive"))
      (node (ref "D2") (pin "G23") (pinfunction "VCCRSTCLK_HPS_G23") (pintype "power_in"))
      (node (ref "D2") (pin "J20") (pinfunction "VCCRSTCLK_HPS_J20") (pintype "power_in"))
      (node (ref "L6") (pin "2") (pinfunction "2_2") (pintype "passive"))
    )
    (net (code "15") (name "VCC_BAT") (class "Default")
      (node (ref "C188") (pin "1") (pinfunction "+_1") (pintype "passive"))
      (node (ref "D2") (pin "H9") (pinfunction "VCCBAT_H9") (pintype "power_in"))
    )
  )
)
